# as14120_x31_fpga_ddr.net
KiCad netlist of a schematic drawn in Altium Designer
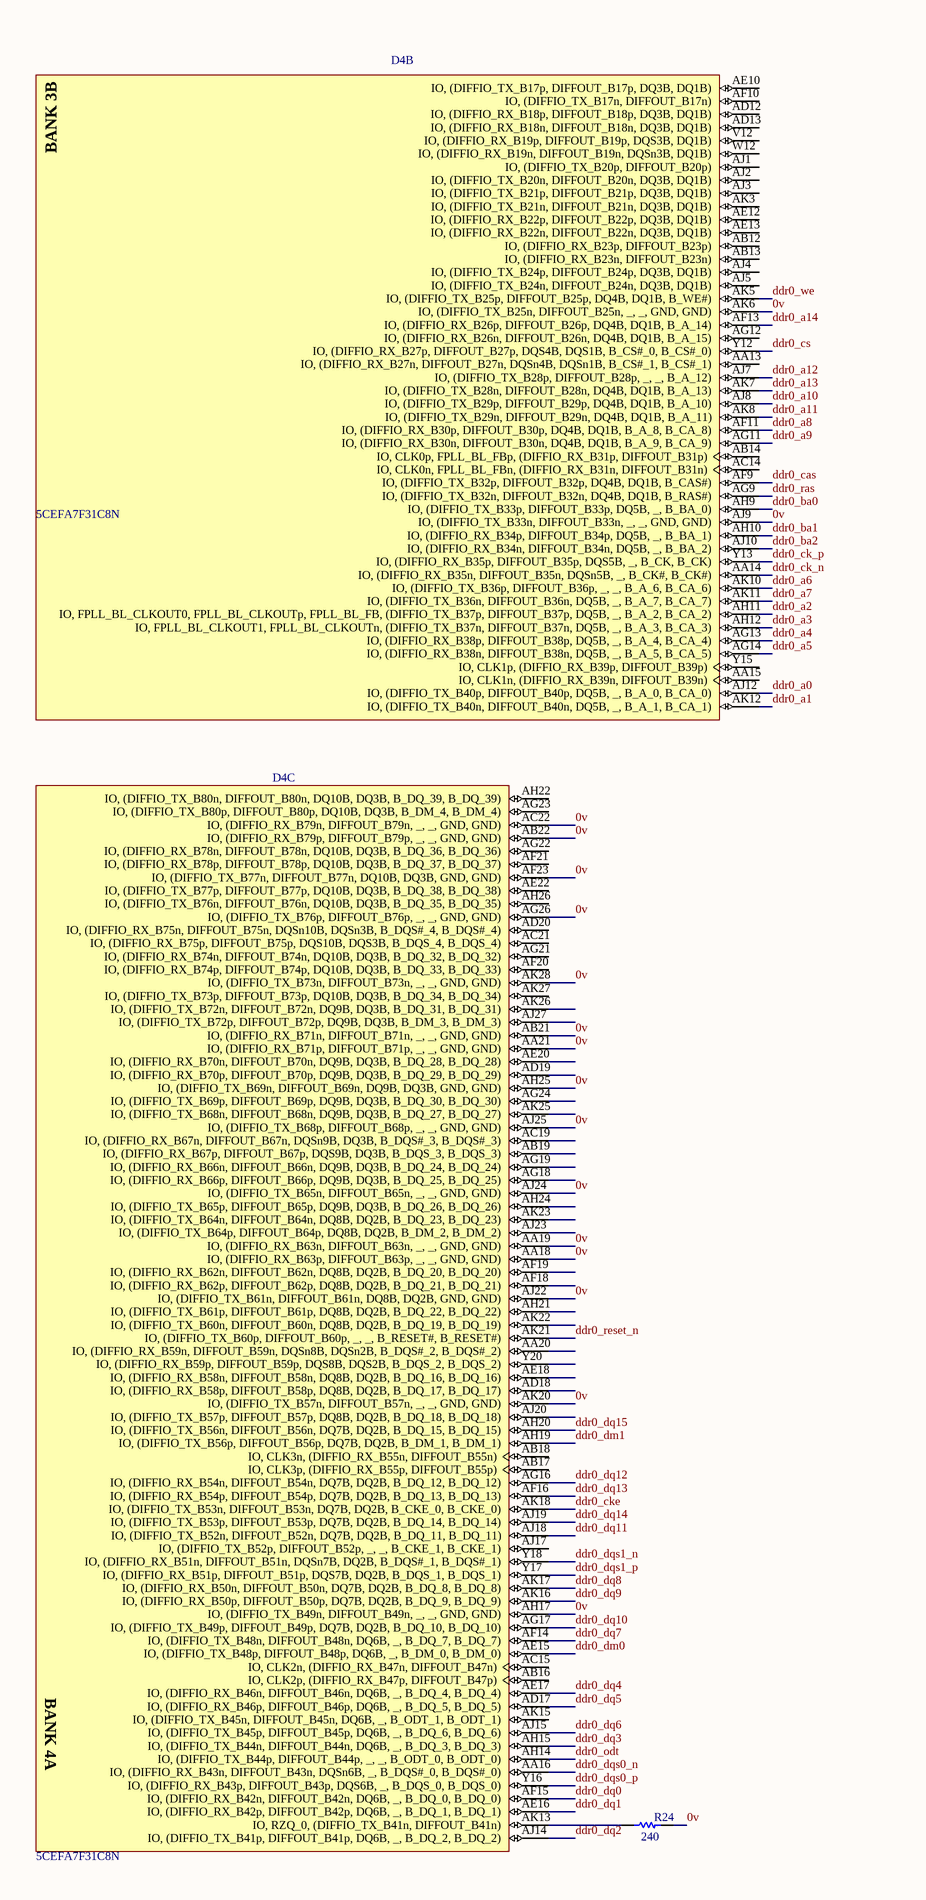
[diagram p0: as14120_x31_fpga_ddr.SchDoc, left]
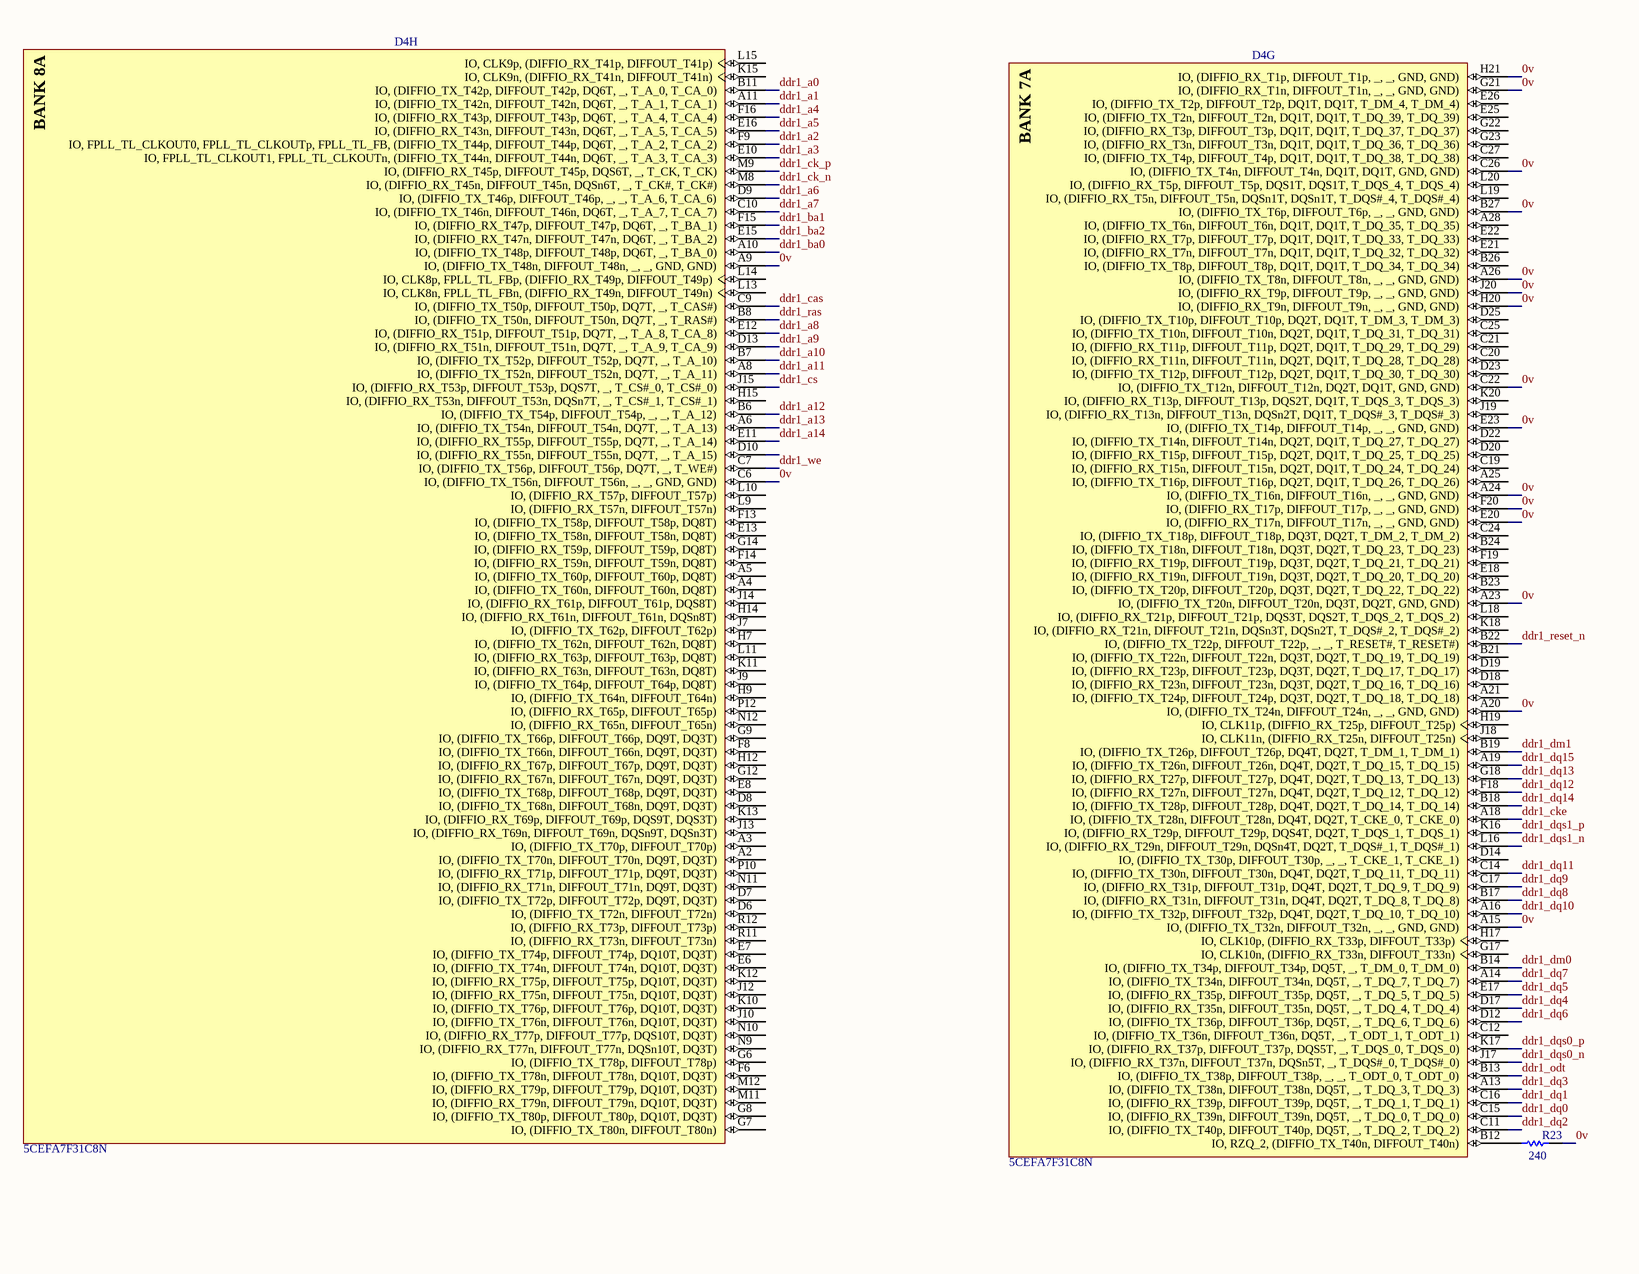
[diagram p1: as14120_x31_fpga_ddr.SchDoc, right]

(export (version "E")
  (design (tool "Eeschema 10.0.6"))
  (components
    (comp (ref "D4")
      (value "5CEFA7F31C8N")
      (footprint "ALTR-896-FBGA-2000A")
      (fields (field (name "MANUFACTURER") "Altera"))
      (libsource (lib "Altera Cyclone V E") (part "5CEFA7F31C8N"))
    )
    (comp (ref "R23")
      (value "240")
      (footprint "RESC0805(2012)_L")
      (description "1K 0.125W 1% 0805 (2012 Metric)  SMD")
      (fields (field (name "TOLERANCE") "1 %") (field (name "POWER") "0.125 W"))
      (libsource (lib "as14120") (part "RES_0805"))
    )
    (comp (ref "R24")
      (value "240")
      (footprint "RESC0805(2012)_L")
      (description "1K 0.125W 1% 0805 (2012 Metric)  SMD")
      (fields (field (name "TOLERANCE") "1 %") (field (name "POWER") "0.125 W"))
      (libsource (lib "as14120") (part "RES_0805"))
    )
  )
  (nets
    (net (code "1") (name "/0v") (class "Default")
      (node (ref "D4") (pin "A15") (pinfunction "IO,_(DIFFIO_TX_T32n,_DIFFOUT_T32n,__,__,_GND,_GND)_A15") (pintype "bidirectional"))
      (node (ref "D4") (pin "A20") (pinfunction "IO,_(DIFFIO_TX_T24n,_DIFFOUT_T24n,__,__,_GND,_GND)_A20") (pintype "bidirectional"))
      (node (ref "D4") (pin "A23") (pinfunction "IO,_(DIFFIO_TX_T20n,_DIFFOUT_T20n,_DQ3T,_DQ2T,_GND,_GND)_A23") (pintype "bidirectional"))
      (node (ref "D4") (pin "A24") (pinfunction "IO,_(DIFFIO_TX_T16n,_DIFFOUT_T16n,__,__,_GND,_GND)_A24") (pintype "bidirectional"))
      (node (ref "D4") (pin "A26") (pinfunction "IO,_(DIFFIO_TX_T8n,_DIFFOUT_T8n,__,__,_GND,_GND)_A26") (pintype "bidirectional"))
      (node (ref "D4") (pin "A9") (pinfunction "IO,_(DIFFIO_TX_T48n,_DIFFOUT_T48n,__,__,_GND,_GND)_A9") (pintype "bidirectional"))
      (node (ref "D4") (pin "AA18") (pinfunction "IO,_(DIFFIO_RX_B63p,_DIFFOUT_B63p,__,__,_GND,_GND)_AA18") (pintype "bidirectional"))
      (node (ref "D4") (pin "AA19") (pinfunction "IO,_(DIFFIO_RX_B63n,_DIFFOUT_B63n,__,__,_GND,_GND)_AA19") (pintype "bidirectional"))
      (node (ref "D4") (pin "AA21") (pinfunction "IO,_(DIFFIO_RX_B71p,_DIFFOUT_B71p,__,__,_GND,_GND)_AA21") (pintype "bidirectional"))
      (node (ref "D4") (pin "AB21") (pinfunction "IO,_(DIFFIO_RX_B71n,_DIFFOUT_B71n,__,__,_GND,_GND)_AB21") (pintype "bidirectional"))
      (node (ref "D4") (pin "AB22") (pinfunction "IO,_(DIFFIO_RX_B79p,_DIFFOUT_B79p,__,__,_GND,_GND)_AB22") (pintype "bidirectional"))
      (node (ref "D4") (pin "AC22") (pinfunction "IO,_(DIFFIO_RX_B79n,_DIFFOUT_B79n,__,__,_GND,_GND)_AC22") (pintype "bidirectional"))
      (node (ref "D4") (pin "AF23") (pinfunction "IO,_(DIFFIO_TX_B77n,_DIFFOUT_B77n,_DQ10B,_DQ3B,_GND,_GND)_AF23") (pintype "bidirectional"))
      (node (ref "D4") (pin "AG26") (pinfunction "IO,_(DIFFIO_TX_B76p,_DIFFOUT_B76p,__,__,_GND,_GND)_AG26") (pintype "bidirectional"))
      (node (ref "D4") (pin "AH17") (pinfunction "IO,_(DIFFIO_TX_B49n,_DIFFOUT_B49n,__,__,_GND,_GND)_AH17") (pintype "bidirectional"))
      (node (ref "D4") (pin "AH25") (pinfunction "IO,_(DIFFIO_TX_B69n,_DIFFOUT_B69n,_DQ9B,_DQ3B,_GND,_GND)_AH25") (pintype "bidirectional"))
      (node (ref "D4") (pin "AJ22") (pinfunction "IO,_(DIFFIO_TX_B61n,_DIFFOUT_B61n,_DQ8B,_DQ2B,_GND,_GND)_AJ22") (pintype "bidirectional"))
      (node (ref "D4") (pin "AJ24") (pinfunction "IO,_(DIFFIO_TX_B65n,_DIFFOUT_B65n,__,__,_GND,_GND)_AJ24") (pintype "bidirectional"))
      (node (ref "D4") (pin "AJ25") (pinfunction "IO,_(DIFFIO_TX_B68p,_DIFFOUT_B68p,__,__,_GND,_GND)_AJ25") (pintype "bidirectional"))
      (node (ref "D4") (pin "AJ9") (pinfunction "IO,_(DIFFIO_TX_B33n,_DIFFOUT_B33n,__,__,_GND,_GND)_AJ9") (pintype "bidirectional"))
      (node (ref "D4") (pin "AK20") (pinfunction "IO,_(DIFFIO_TX_B57n,_DIFFOUT_B57n,__,__,_GND,_GND)_AK20") (pintype "bidirectional"))
      (node (ref "D4") (pin "AK28") (pinfunction "IO,_(DIFFIO_TX_B73n,_DIFFOUT_B73n,__,__,_GND,_GND)_AK28") (pintype "bidirectional"))
      (node (ref "D4") (pin "AK6") (pinfunction "IO,_(DIFFIO_TX_B25n,_DIFFOUT_B25n,__,__,_GND,_GND)_AK6") (pintype "bidirectional"))
      (node (ref "D4") (pin "B27") (pinfunction "IO,_(DIFFIO_TX_T6p,_DIFFOUT_T6p,__,__,_GND,_GND)_B27") (pintype "bidirectional"))
      (node (ref "D4") (pin "C22") (pinfunction "IO,_(DIFFIO_TX_T12n,_DIFFOUT_T12n,_DQ2T,_DQ1T,_GND,_GND)_C22") (pintype "bidirectional"))
      (node (ref "D4") (pin "C26") (pinfunction "IO,_(DIFFIO_TX_T4n,_DIFFOUT_T4n,_DQ1T,_DQ1T,_GND,_GND)_C26") (pintype "bidirectional"))
      (node (ref "D4") (pin "C6") (pinfunction "IO,_(DIFFIO_TX_T56n,_DIFFOUT_T56n,__,__,_GND,_GND)_C6") (pintype "bidirectional"))
      (node (ref "D4") (pin "E20") (pinfunction "IO,_(DIFFIO_RX_T17n,_DIFFOUT_T17n,__,__,_GND,_GND)_E20") (pintype "bidirectional"))
      (node (ref "D4") (pin "E23") (pinfunction "IO,_(DIFFIO_TX_T14p,_DIFFOUT_T14p,__,__,_GND,_GND)_E23") (pintype "bidirectional"))
      (node (ref "D4") (pin "F20") (pinfunction "IO,_(DIFFIO_RX_T17p,_DIFFOUT_T17p,__,__,_GND,_GND)_F20") (pintype "bidirectional"))
      (node (ref "D4") (pin "G21") (pinfunction "IO,_(DIFFIO_RX_T1n,_DIFFOUT_T1n,__,__,_GND,_GND)_G21") (pintype "bidirectional"))
      (node (ref "D4") (pin "H20") (pinfunction "IO,_(DIFFIO_RX_T9n,_DIFFOUT_T9n,__,__,_GND,_GND)_H20") (pintype "bidirectional"))
      (node (ref "D4") (pin "H21") (pinfunction "IO,_(DIFFIO_RX_T1p,_DIFFOUT_T1p,__,__,_GND,_GND)_H21") (pintype "bidirectional"))
      (node (ref "D4") (pin "J20") (pinfunction "IO,_(DIFFIO_RX_T9p,_DIFFOUT_T9p,__,__,_GND,_GND)_J20") (pintype "bidirectional"))
      (node (ref "R23") (pin "2") (pinfunction "2_2") (pintype "passive"))
      (node (ref "R24") (pin "2") (pinfunction "2_2") (pintype "passive"))
    )
    (net (code "2") (name "/ddr0_a0") (class "Default")
      (node (ref "D4") (pin "AJ12") (pinfunction "IO,_(DIFFIO_TX_B40p,_DIFFOUT_B40p,_DQ5B,__,_B_A_0,_B_CA_0)_AJ12") (pintype "bidirectional"))
    )
    (net (code "3") (name "/ddr0_a1") (class "Default")
      (node (ref "D4") (pin "AK12") (pinfunction "IO,_(DIFFIO_TX_B40n,_DIFFOUT_B40n,_DQ5B,__,_B_A_1,_B_CA_1)_AK12") (pintype "bidirectional"))
    )
    (net (code "4") (name "/ddr0_a2") (class "Default")
      (node (ref "D4") (pin "AH11") (pinfunction "IO,_FPLL_BL_CLKOUT0,_FPLL_BL_CLKOUTp,_FPLL_BL_FB,_(DIFFIO_TX_B37p,_DIFFOUT_B37p,_DQ5B,__,_B_A_2,_B_CA_2)_AH11") (pintype "bidirectional"))
    )
    (net (code "5") (name "/ddr0_a3") (class "Default")
      (node (ref "D4") (pin "AH12") (pinfunction "IO,_FPLL_BL_CLKOUT1,_FPLL_BL_CLKOUTn,_(DIFFIO_TX_B37n,_DIFFOUT_B37n,_DQ5B,__,_B_A_3,_B_CA_3)_AH12") (pintype "bidirectional"))
    )
    (net (code "6") (name "/ddr0_a4") (class "Default")
      (node (ref "D4") (pin "AG13") (pinfunction "IO,_(DIFFIO_RX_B38p,_DIFFOUT_B38p,_DQ5B,__,_B_A_4,_B_CA_4)_AG13") (pintype "bidirectional"))
    )
    (net (code "7") (name "/ddr0_a5") (class "Default")
      (node (ref "D4") (pin "AG14") (pinfunction "IO,_(DIFFIO_RX_B38n,_DIFFOUT_B38n,_DQ5B,__,_B_A_5,_B_CA_5)_AG14") (pintype "bidirectional"))
    )
    (net (code "8") (name "/ddr0_a6") (class "Default")
      (node (ref "D4") (pin "AK10") (pinfunction "IO,_(DIFFIO_TX_B36p,_DIFFOUT_B36p,__,__,_B_A_6,_B_CA_6)_AK10") (pintype "bidirectional"))
    )
    (net (code "9") (name "/ddr0_a7") (class "Default")
      (node (ref "D4") (pin "AK11") (pinfunction "IO,_(DIFFIO_TX_B36n,_DIFFOUT_B36n,_DQ5B,__,_B_A_7,_B_CA_7)_AK11") (pintype "bidirectional"))
    )
    (net (code "10") (name "/ddr0_a8") (class "Default")
      (node (ref "D4") (pin "AF11") (pinfunction "IO,_(DIFFIO_RX_B30p,_DIFFOUT_B30p,_DQ4B,_DQ1B,_B_A_8,_B_CA_8)_AF11") (pintype "bidirectional"))
    )
    (net (code "11") (name "/ddr0_a9") (class "Default")
      (node (ref "D4") (pin "AG11") (pinfunction "IO,_(DIFFIO_RX_B30n,_DIFFOUT_B30n,_DQ4B,_DQ1B,_B_A_9,_B_CA_9)_AG11") (pintype "bidirectional"))
    )
    (net (code "12") (name "/ddr0_a10") (class "Default")
      (node (ref "D4") (pin "AJ8") (pinfunction "IO,_(DIFFIO_TX_B29p,_DIFFOUT_B29p,_DQ4B,_DQ1B,_B_A_10)_AJ8") (pintype "bidirectional"))
    )
    (net (code "13") (name "/ddr0_a11") (class "Default")
      (node (ref "D4") (pin "AK8") (pinfunction "IO,_(DIFFIO_TX_B29n,_DIFFOUT_B29n,_DQ4B,_DQ1B,_B_A_11)_AK8") (pintype "bidirectional"))
    )
    (net (code "14") (name "/ddr0_a12") (class "Default")
      (node (ref "D4") (pin "AJ7") (pinfunction "IO,_(DIFFIO_TX_B28p,_DIFFOUT_B28p,__,__,_B_A_12)_AJ7") (pintype "bidirectional"))
    )
    (net (code "15") (name "/ddr0_a13") (class "Default")
      (node (ref "D4") (pin "AK7") (pinfunction "IO,_(DIFFIO_TX_B28n,_DIFFOUT_B28n,_DQ4B,_DQ1B,_B_A_13)_AK7") (pintype "bidirectional"))
    )
    (net (code "16") (name "/ddr0_a14") (class "Default")
      (node (ref "D4") (pin "AF13") (pinfunction "IO,_(DIFFIO_RX_B26p,_DIFFOUT_B26p,_DQ4B,_DQ1B,_B_A_14)_AF13") (pintype "bidirectional"))
    )
    (net (code "17") (name "/ddr0_ba0") (class "Default")
      (node (ref "D4") (pin "AH9") (pinfunction "IO,_(DIFFIO_TX_B33p,_DIFFOUT_B33p,_DQ5B,__,_B_BA_0)_AH9") (pintype "bidirectional"))
    )
    (net (code "18") (name "/ddr0_ba1") (class "Default")
      (node (ref "D4") (pin "AH10") (pinfunction "IO,_(DIFFIO_RX_B34p,_DIFFOUT_B34p,_DQ5B,__,_B_BA_1)_AH10") (pintype "bidirectional"))
    )
    (net (code "19") (name "/ddr0_ba2") (class "Default")
      (node (ref "D4") (pin "AJ10") (pinfunction "IO,_(DIFFIO_RX_B34n,_DIFFOUT_B34n,_DQ5B,__,_B_BA_2)_AJ10") (pintype "bidirectional"))
    )
    (net (code "20") (name "/ddr0_cas") (class "Default")
      (node (ref "D4") (pin "AF9") (pinfunction "IO,_(DIFFIO_TX_B32p,_DIFFOUT_B32p,_DQ4B,_DQ1B,_B_CAS#)_AF9") (pintype "bidirectional"))
    )
    (net (code "21") (name "/ddr0_ck_n") (class "Default")
      (node (ref "D4") (pin "AA14") (pinfunction "IO,_(DIFFIO_RX_B35n,_DIFFOUT_B35n,_DQSn5B,__,_B_CK#,_B_CK#)_AA14") (pintype "bidirectional"))
    )
    (net (code "22") (name "/ddr0_ck_p") (class "Default")
      (node (ref "D4") (pin "Y13") (pinfunction "IO,_(DIFFIO_RX_B35p,_DIFFOUT_B35p,_DQS5B,__,_B_CK,_B_CK)_Y13") (pintype "bidirectional"))
    )
    (net (code "23") (name "/ddr0_cke") (class "Default")
      (node (ref "D4") (pin "AK18") (pinfunction "IO,_(DIFFIO_TX_B53n,_DIFFOUT_B53n,_DQ7B,_DQ2B,_B_CKE_0,_B_CKE_0)_AK18") (pintype "bidirectional"))
    )
    (net (code "24") (name "/ddr0_cs") (class "Default")
      (node (ref "D4") (pin "Y12") (pinfunction "IO,_(DIFFIO_RX_B27p,_DIFFOUT_B27p,_DQS4B,_DQS1B,_B_CS#_0,_B_CS#_0)_Y12") (pintype "bidirectional"))
    )
    (net (code "25") (name "/ddr0_dm0") (class "Default")
      (node (ref "D4") (pin "AE15") (pinfunction "IO,_(DIFFIO_TX_B48p,_DIFFOUT_B48p,_DQ6B,__,_B_DM_0,_B_DM_0)_AE15") (pintype "bidirectional"))
    )
    (net (code "26") (name "/ddr0_dm1") (class "Default")
      (node (ref "D4") (pin "AH19") (pinfunction "IO,_(DIFFIO_TX_B56p,_DIFFOUT_B56p,_DQ7B,_DQ2B,_B_DM_1,_B_DM_1)_AH19") (pintype "bidirectional"))
    )
    (net (code "27") (name "/ddr0_dq0") (class "Default")
      (node (ref "D4") (pin "AF15") (pinfunction "IO,_(DIFFIO_RX_B42n,_DIFFOUT_B42n,_DQ6B,__,_B_DQ_0,_B_DQ_0)_AF15") (pintype "bidirectional"))
    )
    (net (code "28") (name "/ddr0_dq1") (class "Default")
      (node (ref "D4") (pin "AE16") (pinfunction "IO,_(DIFFIO_RX_B42p,_DIFFOUT_B42p,_DQ6B,__,_B_DQ_1,_B_DQ_1)_AE16") (pintype "bidirectional"))
    )
    (net (code "29") (name "/ddr0_dq2") (class "Default")
      (node (ref "D4") (pin "AJ14") (pinfunction "IO,_(DIFFIO_TX_B41p,_DIFFOUT_B41p,_DQ6B,__,_B_DQ_2,_B_DQ_2)_AJ14") (pintype "bidirectional"))
    )
    (net (code "30") (name "/ddr0_dq3") (class "Default")
      (node (ref "D4") (pin "AH15") (pinfunction "IO,_(DIFFIO_TX_B44n,_DIFFOUT_B44n,_DQ6B,__,_B_DQ_3,_B_DQ_3)_AH15") (pintype "bidirectional"))
    )
    (net (code "31") (name "/ddr0_dq4") (class "Default")
      (node (ref "D4") (pin "AE17") (pinfunction "IO,_(DIFFIO_RX_B46n,_DIFFOUT_B46n,_DQ6B,__,_B_DQ_4,_B_DQ_4)_AE17") (pintype "bidirectional"))
    )
    (net (code "32") (name "/ddr0_dq5") (class "Default")
      (node (ref "D4") (pin "AD17") (pinfunction "IO,_(DIFFIO_RX_B46p,_DIFFOUT_B46p,_DQ6B,__,_B_DQ_5,_B_DQ_5)_AD17") (pintype "bidirectional"))
    )
    (net (code "33") (name "/ddr0_dq6") (class "Default")
      (node (ref "D4") (pin "AJ15") (pinfunction "IO,_(DIFFIO_TX_B45p,_DIFFOUT_B45p,_DQ6B,__,_B_DQ_6,_B_DQ_6)_AJ15") (pintype "bidirectional"))
    )
    (net (code "34") (name "/ddr0_dq7") (class "Default")
      (node (ref "D4") (pin "AF14") (pinfunction "IO,_(DIFFIO_TX_B48n,_DIFFOUT_B48n,_DQ6B,__,_B_DQ_7,_B_DQ_7)_AF14") (pintype "bidirectional"))
    )
    (net (code "35") (name "/ddr0_dq8") (class "Default")
      (node (ref "D4") (pin "AK17") (pinfunction "IO,_(DIFFIO_RX_B50n,_DIFFOUT_B50n,_DQ7B,_DQ2B,_B_DQ_8,_B_DQ_8)_AK17") (pintype "bidirectional"))
    )
    (net (code "36") (name "/ddr0_dq9") (class "Default")
      (node (ref "D4") (pin "AK16") (pinfunction "IO,_(DIFFIO_RX_B50p,_DIFFOUT_B50p,_DQ7B,_DQ2B,_B_DQ_9,_B_DQ_9)_AK16") (pintype "bidirectional"))
    )
    (net (code "37") (name "/ddr0_dq10") (class "Default")
      (node (ref "D4") (pin "AG17") (pinfunction "IO,_(DIFFIO_TX_B49p,_DIFFOUT_B49p,_DQ7B,_DQ2B,_B_DQ_10,_B_DQ_10)_AG17") (pintype "bidirectional"))
    )
    (net (code "38") (name "/ddr0_dq11") (class "Default")
      (node (ref "D4") (pin "AJ18") (pinfunction "IO,_(DIFFIO_TX_B52n,_DIFFOUT_B52n,_DQ7B,_DQ2B,_B_DQ_11,_B_DQ_11)_AJ18") (pintype "bidirectional"))
    )
    (net (code "39") (name "/ddr0_dq12") (class "Default")
      (node (ref "D4") (pin "AG16") (pinfunction "IO,_(DIFFIO_RX_B54n,_DIFFOUT_B54n,_DQ7B,_DQ2B,_B_DQ_12,_B_DQ_12)_AG16") (pintype "bidirectional"))
    )
    (net (code "40") (name "/ddr0_dq13") (class "Default")
      (node (ref "D4") (pin "AF16") (pinfunction "IO,_(DIFFIO_RX_B54p,_DIFFOUT_B54p,_DQ7B,_DQ2B,_B_DQ_13,_B_DQ_13)_AF16") (pintype "bidirectional"))
    )
    (net (code "41") (name "/ddr0_dq14") (class "Default")
      (node (ref "D4") (pin "AJ19") (pinfunction "IO,_(DIFFIO_TX_B53p,_DIFFOUT_B53p,_DQ7B,_DQ2B,_B_DQ_14,_B_DQ_14)_AJ19") (pintype "bidirectional"))
    )
    (net (code "42") (name "/ddr0_dq15") (class "Default")
      (node (ref "D4") (pin "AH20") (pinfunction "IO,_(DIFFIO_TX_B56n,_DIFFOUT_B56n,_DQ7B,_DQ2B,_B_DQ_15,_B_DQ_15)_AH20") (pintype "bidirectional"))
    )
    (net (code "43") (name "/ddr0_dqs0_n") (class "Default")
      (node (ref "D4") (pin "AA16") (pinfunction "IO,_(DIFFIO_RX_B43n,_DIFFOUT_B43n,_DQSn6B,__,_B_DQS#_0,_B_DQS#_0)_AA16") (pintype "bidirectional"))
    )
    (net (code "44") (name "/ddr0_dqs0_p") (class "Default")
      (node (ref "D4") (pin "Y16") (pinfunction "IO,_(DIFFIO_RX_B43p,_DIFFOUT_B43p,_DQS6B,__,_B_DQS_0,_B_DQS_0)_Y16") (pintype "bidirectional"))
    )
    (net (code "45") (name "/ddr0_dqs1_n") (class "Default")
      (node (ref "D4") (pin "Y18") (pinfunction "IO,_(DIFFIO_RX_B51n,_DIFFOUT_B51n,_DQSn7B,_DQ2B,_B_DQS#_1,_B_DQS#_1)_Y18") (pintype "bidirectional"))
    )
    (net (code "46") (name "/ddr0_dqs1_p") (class "Default")
      (node (ref "D4") (pin "Y17") (pinfunction "IO,_(DIFFIO_RX_B51p,_DIFFOUT_B51p,_DQS7B,_DQ2B,_B_DQS_1,_B_DQS_1)_Y17") (pintype "bidirectional"))
    )
    (net (code "47") (name "/ddr0_odt") (class "Default")
      (node (ref "D4") (pin "AH14") (pinfunction "IO,_(DIFFIO_TX_B44p,_DIFFOUT_B44p,__,__,_B_ODT_0,_B_ODT_0)_AH14") (pintype "bidirectional"))
    )
    (net (code "48") (name "/ddr0_ras") (class "Default")
      (node (ref "D4") (pin "AG9") (pinfunction "IO,_(DIFFIO_TX_B32n,_DIFFOUT_B32n,_DQ4B,_DQ1B,_B_RAS#)_AG9") (pintype "bidirectional"))
    )
    (net (code "49") (name "/ddr0_reset_n") (class "Default")
      (node (ref "D4") (pin "AK21") (pinfunction "IO,_(DIFFIO_TX_B60p,_DIFFOUT_B60p,__,__,_B_RESET#,_B_RESET#)_AK21") (pintype "bidirectional"))
    )
    (net (code "50") (name "/ddr0_we") (class "Default")
      (node (ref "D4") (pin "AK5") (pinfunction "IO,_(DIFFIO_TX_B25p,_DIFFOUT_B25p,_DQ4B,_DQ1B,_B_WE#)_AK5") (pintype "bidirectional"))
    )
    (net (code "51") (name "/ddr1_a0") (class "Default")
      (node (ref "D4") (pin "B11") (pinfunction "IO,_(DIFFIO_TX_T42p,_DIFFOUT_T42p,_DQ6T,__,_T_A_0,_T_CA_0)_B11") (pintype "bidirectional"))
    )
    (net (code "52") (name "/ddr1_a1") (class "Default")
      (node (ref "D4") (pin "A11") (pinfunction "IO,_(DIFFIO_TX_T42n,_DIFFOUT_T42n,_DQ6T,__,_T_A_1,_T_CA_1)_A11") (pintype "bidirectional"))
    )
    (net (code "53") (name "/ddr1_a2") (class "Default")
      (node (ref "D4") (pin "F9") (pinfunction "IO,_FPLL_TL_CLKOUT0,_FPLL_TL_CLKOUTp,_FPLL_TL_FB,_(DIFFIO_TX_T44p,_DIFFOUT_T44p,_DQ6T,__,_T_A_2,_T_CA_2)_F9") (pintype "bidirectional"))
    )
    (net (code "54") (name "/ddr1_a3") (class "Default")
      (node (ref "D4") (pin "E10") (pinfunction "IO,_FPLL_TL_CLKOUT1,_FPLL_TL_CLKOUTn,_(DIFFIO_TX_T44n,_DIFFOUT_T44n,_DQ6T,__,_T_A_3,_T_CA_3)_E10") (pintype "bidirectional"))
    )
    (net (code "55") (name "/ddr1_a4") (class "Default")
      (node (ref "D4") (pin "F16") (pinfunction "IO,_(DIFFIO_RX_T43p,_DIFFOUT_T43p,_DQ6T,__,_T_A_4,_T_CA_4)_F16") (pintype "bidirectional"))
    )
    (net (code "56") (name "/ddr1_a5") (class "Default")
      (node (ref "D4") (pin "E16") (pinfunction "IO,_(DIFFIO_RX_T43n,_DIFFOUT_T43n,_DQ6T,__,_T_A_5,_T_CA_5)_E16") (pintype "bidirectional"))
    )
    (net (code "57") (name "/ddr1_a6") (class "Default")
      (node (ref "D4") (pin "D9") (pinfunction "IO,_(DIFFIO_TX_T46p,_DIFFOUT_T46p,__,__,_T_A_6,_T_CA_6)_D9") (pintype "bidirectional"))
    )
    (net (code "58") (name "/ddr1_a7") (class "Default")
      (node (ref "D4") (pin "C10") (pinfunction "IO,_(DIFFIO_TX_T46n,_DIFFOUT_T46n,_DQ6T,__,_T_A_7,_T_CA_7)_C10") (pintype "bidirectional"))
    )
    (net (code "59") (name "/ddr1_a8") (class "Default")
      (node (ref "D4") (pin "E12") (pinfunction "IO,_(DIFFIO_RX_T51p,_DIFFOUT_T51p,_DQ7T,__,_T_A_8,_T_CA_8)_E12") (pintype "bidirectional"))
    )
    (net (code "60") (name "/ddr1_a9") (class "Default")
      (node (ref "D4") (pin "D13") (pinfunction "IO,_(DIFFIO_RX_T51n,_DIFFOUT_T51n,_DQ7T,__,_T_A_9,_T_CA_9)_D13") (pintype "bidirectional"))
    )
    (net (code "61") (name "/ddr1_a10") (class "Default")
      (node (ref "D4") (pin "B7") (pinfunction "IO,_(DIFFIO_TX_T52p,_DIFFOUT_T52p,_DQ7T,__,_T_A_10)_B7") (pintype "bidirectional"))
    )
    (net (code "62") (name "/ddr1_a11") (class "Default")
      (node (ref "D4") (pin "A8") (pinfunction "IO,_(DIFFIO_TX_T52n,_DIFFOUT_T52n,_DQ7T,__,_T_A_11)_A8") (pintype "bidirectional"))
    )
    (net (code "63") (name "/ddr1_a12") (class "Default")
      (node (ref "D4") (pin "B6") (pinfunction "IO,_(DIFFIO_TX_T54p,_DIFFOUT_T54p,__,__,_T_A_12)_B6") (pintype "bidirectional"))
    )
    (net (code "64") (name "/ddr1_a13") (class "Default")
      (node (ref "D4") (pin "A6") (pinfunction "IO,_(DIFFIO_TX_T54n,_DIFFOUT_T54n,_DQ7T,__,_T_A_13)_A6") (pintype "bidirectional"))
    )
    (net (code "65") (name "/ddr1_a14") (class "Default")
      (node (ref "D4") (pin "E11") (pinfunction "IO,_(DIFFIO_RX_T55p,_DIFFOUT_T55p,_DQ7T,__,_T_A_14)_E11") (pintype "bidirectional"))
    )
    (net (code "66") (name "/ddr1_ba0") (class "Default")
      (node (ref "D4") (pin "A10") (pinfunction "IO,_(DIFFIO_TX_T48p,_DIFFOUT_T48p,_DQ6T,__,_T_BA_0)_A10") (pintype "bidirectional"))
    )
    (net (code "67") (name "/ddr1_ba1") (class "Default")
      (node (ref "D4") (pin "F15") (pinfunction "IO,_(DIFFIO_RX_T47p,_DIFFOUT_T47p,_DQ6T,__,_T_BA_1)_F15") (pintype "bidirectional"))
    )
    (net (code "68") (name "/ddr1_ba2") (class "Default")
      (node (ref "D4") (pin "E15") (pinfunction "IO,_(DIFFIO_RX_T47n,_DIFFOUT_T47n,_DQ6T,__,_T_BA_2)_E15") (pintype "bidirectional"))
    )
    (net (code "69") (name "/ddr1_cas") (class "Default")
      (node (ref "D4") (pin "C9") (pinfunction "IO,_(DIFFIO_TX_T50p,_DIFFOUT_T50p,_DQ7T,__,_T_CAS#)_C9") (pintype "bidirectional"))
    )
    (net (code "70") (name "/ddr1_ck_n") (class "Default")
      (node (ref "D4") (pin "M8") (pinfunction "IO,_(DIFFIO_RX_T45n,_DIFFOUT_T45n,_DQSn6T,__,_T_CK#,_T_CK#)_M8") (pintype "bidirectional"))
    )
    (net (code "71") (name "/ddr1_ck_p") (class "Default")
      (node (ref "D4") (pin "M9") (pinfunction "IO,_(DIFFIO_RX_T45p,_DIFFOUT_T45p,_DQS6T,__,_T_CK,_T_CK)_M9") (pintype "bidirectional"))
    )
    (net (code "72") (name "/ddr1_cke") (class "Default")
      (node (ref "D4") (pin "A18") (pinfunction "IO,_(DIFFIO_TX_T28n,_DIFFOUT_T28n,_DQ4T,_DQ2T,_T_CKE_0,_T_CKE_0)_A18") (pintype "bidirectional"))
    )
    (net (code "73") (name "/ddr1_cs") (class "Default")
      (node (ref "D4") (pin "J15") (pinfunction "IO,_(DIFFIO_RX_T53p,_DIFFOUT_T53p,_DQS7T,__,_T_CS#_0,_T_CS#_0)_J15") (pintype "bidirectional"))
    )
    (net (code "74") (name "/ddr1_dm0") (class "Default")
      (node (ref "D4") (pin "B14") (pinfunction "IO,_(DIFFIO_TX_T34p,_DIFFOUT_T34p,_DQ5T,__,_T_DM_0,_T_DM_0)_B14") (pintype "bidirectional"))
    )
    (net (code "75") (name "/ddr1_dm1") (class "Default")
      (node (ref "D4") (pin "B19") (pinfunction "IO,_(DIFFIO_TX_T26p,_DIFFOUT_T26p,_DQ4T,_DQ2T,_T_DM_1,_T_DM_1)_B19") (pintype "bidirectional"))
    )
    (net (code "76") (name "/ddr1_dq0") (class "Default")
      (node (ref "D4") (pin "C15") (pinfunction "IO,_(DIFFIO_RX_T39n,_DIFFOUT_T39n,_DQ5T,__,_T_DQ_0,_T_DQ_0)_C15") (pintype "bidirectional"))
    )
    (net (code "77") (name "/ddr1_dq1") (class "Default")
      (node (ref "D4") (pin "C16") (pinfunction "IO,_(DIFFIO_RX_T39p,_DIFFOUT_T39p,_DQ5T,__,_T_DQ_1,_T_DQ_1)_C16") (pintype "bidirectional"))
    )
    (net (code "78") (name "/ddr1_dq2") (class "Default")
      (node (ref "D4") (pin "C11") (pinfunction "IO,_(DIFFIO_TX_T40p,_DIFFOUT_T40p,_DQ5T,__,_T_DQ_2,_T_DQ_2)_C11") (pintype "bidirectional"))
    )
    (net (code "79") (name "/ddr1_dq3") (class "Default")
      (node (ref "D4") (pin "A13") (pinfunction "IO,_(DIFFIO_TX_T38n,_DIFFOUT_T38n,_DQ5T,__,_T_DQ_3,_T_DQ_3)_A13") (pintype "bidirectional"))
    )
    (net (code "80") (name "/ddr1_dq4") (class "Default")
      (node (ref "D4") (pin "D17") (pinfunction "IO,_(DIFFIO_RX_T35n,_DIFFOUT_T35n,_DQ5T,__,_T_DQ_4,_T_DQ_4)_D17") (pintype "bidirectional"))
    )
    (net (code "81") (name "/ddr1_dq5") (class "Default")
      (node (ref "D4") (pin "E17") (pinfunction "IO,_(DIFFIO_RX_T35p,_DIFFOUT_T35p,_DQ5T,__,_T_DQ_5,_T_DQ_5)_E17") (pintype "bidirectional"))
    )
    (net (code "82") (name "/ddr1_dq6") (class "Default")
      (node (ref "D4") (pin "D12") (pinfunction "IO,_(DIFFIO_TX_T36p,_DIFFOUT_T36p,_DQ5T,__,_T_DQ_6,_T_DQ_6)_D12") (pintype "bidirectional"))
    )
    (net (code "83") (name "/ddr1_dq7") (class "Default")
      (node (ref "D4") (pin "A14") (pinfunction "IO,_(DIFFIO_TX_T34n,_DIFFOUT_T34n,_DQ5T,__,_T_DQ_7,_T_DQ_7)_A14") (pintype "bidirectional"))
    )
    (net (code "84") (name "/ddr1_dq8") (class "Default")
      (node (ref "D4") (pin "B17") (pinfunction "IO,_(DIFFIO_RX_T31n,_DIFFOUT_T31n,_DQ4T,_DQ2T,_T_DQ_8,_T_DQ_8)_B17") (pintype "bidirectional"))
    )
    (net (code "85") (name "/ddr1_dq9") (class "Default")
      (node (ref "D4") (pin "C17") (pinfunction "IO,_(DIFFIO_RX_T31p,_DIFFOUT_T31p,_DQ4T,_DQ2T,_T_DQ_9,_T_DQ_9)_C17") (pintype "bidirectional"))
    )
    (net (code "86") (name "/ddr1_dq10") (class "Default")
      (node (ref "D4") (pin "A16") (pinfunction "IO,_(DIFFIO_TX_T32p,_DIFFOUT_T32p,_DQ4T,_DQ2T,_T_DQ_10,_T_DQ_10)_A16") (pintype "bidirectional"))
    )
    (net (code "87") (name "/ddr1_dq11") (class "Default")
      (node (ref "D4") (pin "C14") (pinfunction "IO,_(DIFFIO_TX_T30n,_DIFFOUT_T30n,_DQ4T,_DQ2T,_T_DQ_11,_T_DQ_11)_C14") (pintype "bidirectional"))
    )
    (net (code "88") (name "/ddr1_dq12") (class "Default")
      (node (ref "D4") (pin "F18") (pinfunction "IO,_(DIFFIO_RX_T27n,_DIFFOUT_T27n,_DQ4T,_DQ2T,_T_DQ_12,_T_DQ_12)_F18") (pintype "bidirectional"))
    )
    (net (code "89") (name "/ddr1_dq13") (class "Default")
      (node (ref "D4") (pin "G18") (pinfunction "IO,_(DIFFIO_RX_T27p,_DIFFOUT_T27p,_DQ4T,_DQ2T,_T_DQ_13,_T_DQ_13)_G18") (pintype "bidirectional"))
    )
    (net (code "90") (name "/ddr1_dq14") (class "Default")
      (node (ref "D4") (pin "B18") (pinfunction "IO,_(DIFFIO_TX_T28p,_DIFFOUT_T28p,_DQ4T,_DQ2T,_T_DQ_14,_T_DQ_14)_B18") (pintype "bidirectional"))
    )
    (net (code "91") (name "/ddr1_dq15") (class "Default")
      (node (ref "D4") (pin "A19") (pinfunction "IO,_(DIFFIO_TX_T26n,_DIFFOUT_T26n,_DQ4T,_DQ2T,_T_DQ_15,_T_DQ_15)_A19") (pintype "bidirectional"))
    )
    (net (code "92") (name "/ddr1_dqs0_n") (class "Default")
      (node (ref "D4") (pin "J17") (pinfunction "IO,_(DIFFIO_RX_T37n,_DIFFOUT_T37n,_DQSn5T,__,_T_DQS#_0,_T_DQS#_0)_J17") (pintype "bidirectional"))
    )
    (net (code "93") (name "/ddr1_dqs0_p") (class "Default")
      (node (ref "D4") (pin "K17") (pinfunction "IO,_(DIFFIO_RX_T37p,_DIFFOUT_T37p,_DQS5T,__,_T_DQS_0,_T_DQS_0)_K17") (pintype "bidirectional"))
    )
    (net (code "94") (name "/ddr1_dqs1_n") (class "Default")
      (node (ref "D4") (pin "L16") (pinfunction "IO,_(DIFFIO_RX_T29n,_DIFFOUT_T29n,_DQSn4T,_DQ2T,_T_DQS#_1,_T_DQS#_1)_L16") (pintype "bidirectional"))
    )
    (net (code "95") (name "/ddr1_dqs1_p") (class "Default")
      (node (ref "D4") (pin "K16") (pinfunction "IO,_(DIFFIO_RX_T29p,_DIFFOUT_T29p,_DQS4T,_DQ2T,_T_DQS_1,_T_DQS_1)_K16") (pintype "bidirectional"))
    )
    (net (code "96") (name "/ddr1_odt") (class "Default")
      (node (ref "D4") (pin "B13") (pinfunction "IO,_(DIFFIO_TX_T38p,_DIFFOUT_T38p,__,__,_T_ODT_0,_T_ODT_0)_B13") (pintype "bidirectional"))
    )
    (net (code "97") (name "/ddr1_ras") (class "Default")
      (node (ref "D4") (pin "B8") (pinfunction "IO,_(DIFFIO_TX_T50n,_DIFFOUT_T50n,_DQ7T,__,_T_RAS#)_B8") (pintype "bidirectional"))
    )
    (net (code "98") (name "/ddr1_reset_n") (class "Default")
      (node (ref "D4") (pin "B22") (pinfunction "IO,_(DIFFIO_TX_T22p,_DIFFOUT_T22p,__,__,_T_RESET#,_T_RESET#)_B22") (pintype "bidirectional"))
    )
    (net (code "99") (name "/ddr1_we") (class "Default")
      (node (ref "D4") (pin "C7") (pinfunction "IO,_(DIFFIO_TX_T56p,_DIFFOUT_T56p,_DQ7T,__,_T_WE#)_C7") (pintype "bidirectional"))
    )
    (net (code "100") (name "Net-(D4C-IO,_RZQ_0,_(DIFFIO_TX_B41n,_DIFFOUT_B41n))") (class "Default")
      (node (ref "D4") (pin "AK13") (pinfunction "IO,_RZQ_0,_(DIFFIO_TX_B41n,_DIFFOUT_B41n)_AK13") (pintype "bidirectional"))
      (node (ref "R24") (pin "1") (pinfunction "1_1") (pintype "passive"))
    )
    (net (code "101") (name "Net-(D4G-IO,_RZQ_2,_(DIFFIO_TX_T40n,_DIFFOUT_T40n))") (class "Default")
      (node (ref "D4") (pin "B12") (pinfunction "IO,_RZQ_2,_(DIFFIO_TX_T40n,_DIFFOUT_T40n)_B12") (pintype "bidirectional"))
      (node (ref "R23") (pin "1") (pinfunction "1_1") (pintype "passive"))
    )
    (net (code "102") (name "unconnected-(D4B-IO,_(DIFFIO_RX_B18n,_DIFFOUT_B18n,_DQ3B,_DQ1B)-PadAD13)") (class "Default")
      (node (ref "D4") (pin "AD13") (pinfunction "IO,_(DIFFIO_RX_B18n,_DIFFOUT_B18n,_DQ3B,_DQ1B)_AD13") (pintype "bidirectional"))
    )
    (net (code "103") (name "unconnected-(D4B-IO,_(DIFFIO_RX_B18p,_DIFFOUT_B18p,_DQ3B,_DQ1B)-PadAD12)") (class "Default")
      (node (ref "D4") (pin "AD12") (pinfunction "IO,_(DIFFIO_RX_B18p,_DIFFOUT_B18p,_DQ3B,_DQ1B)_AD12") (pintype "bidirectional"))
    )
    (net (code "104") (name "unconnected-(D4B-IO,_(DIFFIO_RX_B19n,_DIFFOUT_B19n,_DQSn3B,_DQ1B)-PadW12)") (class "Default")
      (node (ref "D4") (pin "W12") (pinfunction "IO,_(DIFFIO_RX_B19n,_DIFFOUT_B19n,_DQSn3B,_DQ1B)_W12") (pintype "bidirectional"))
    )
    (net (code "105") (name "unconnected-(D4B-IO,_(DIFFIO_RX_B19p,_DIFFOUT_B19p,_DQS3B,_DQ1B)-PadV12)") (class "Default")
      (node (ref "D4") (pin "V12") (pinfunction "IO,_(DIFFIO_RX_B19p,_DIFFOUT_B19p,_DQS3B,_DQ1B)_V12") (pintype "bidirectional"))
    )
    (net (code "106") (name "unconnected-(D4B-IO,_(DIFFIO_RX_B22n,_DIFFOUT_B22n,_DQ3B,_DQ1B)-PadAE13)") (class "Default")
      (node (ref "D4") (pin "AE13") (pinfunction "IO,_(DIFFIO_RX_B22n,_DIFFOUT_B22n,_DQ3B,_DQ1B)_AE13") (pintype "bidirectional"))
    )
    (net (code "107") (name "unconnected-(D4B-IO,_(DIFFIO_RX_B22p,_DIFFOUT_B22p,_DQ3B,_DQ1B)-PadAE12)") (class "Default")
      (node (ref "D4") (pin "AE12") (pinfunction "IO,_(DIFFIO_RX_B22p,_DIFFOUT_B22p,_DQ3B,_DQ1B)_AE12") (pintype "bidirectional"))
    )
    (net (code "108") (name "unconnected-(D4B-IO,_(DIFFIO_RX_B23n,_DIFFOUT_B23n)-PadAB13)") (class "Default")
      (node (ref "D4") (pin "AB13") (pinfunction "IO,_(DIFFIO_RX_B23n,_DIFFOUT_B23n)_AB13") (pintype "bidirectional"))
    )
    (net (code "109") (name "unconnected-(D4B-IO,_(DIFFIO_RX_B23p,_DIFFOUT_B23p)-PadAB12)") (class "Default")
      (node (ref "D4") (pin "AB12") (pinfunction "IO,_(DIFFIO_RX_B23p,_DIFFOUT_B23p)_AB12") (pintype "bidirectional"))
    )
    (net (code "110") (name "unconnected-(D4B-IO,_(DIFFIO_RX_B26n,_DIFFOUT_B26n,_DQ4B,_DQ1B,_B_A_15)-PadAG12)") (class "Default")
      (node (ref "D4") (pin "AG12") (pinfunction "IO,_(DIFFIO_RX_B26n,_DIFFOUT_B26n,_DQ4B,_DQ1B,_B_A_15)_AG12") (pintype "bidirectional"))
    )
    (net (code "111") (name "unconnected-(D4B-IO,_(DIFFIO_RX_B27n,_DIFFOUT_B27n,_DQSn4B,_DQSn1B,_B_CS#_1,_B_CS#_1)-PadAA13)") (class "Default")
      (node (ref "D4") (pin "AA13") (pinfunction "IO,_(DIFFIO_RX_B27n,_DIFFOUT_B27n,_DQSn4B,_DQSn1B,_B_CS#_1,_B_CS#_1)_AA13") (pintype "bidirectional"))
    )
    (net (code "112") (name "unconnected-(D4B-IO,_(DIFFIO_TX_B17n,_DIFFOUT_B17n)-PadAF10)") (class "Default")
      (node (ref "D4") (pin "AF10") (pinfunction "IO,_(DIFFIO_TX_B17n,_DIFFOUT_B17n)_AF10") (pintype "bidirectional"))
    )
    (net (code "113") (name "unconnected-(D4B-IO,_(DIFFIO_TX_B17p,_DIFFOUT_B17p,_DQ3B,_DQ1B)-PadAE10)") (class "Default")
      (node (ref "D4") (pin "AE10") (pinfunction "IO,_(DIFFIO_TX_B17p,_DIFFOUT_B17p,_DQ3B,_DQ1B)_AE10") (pintype "bidirectional"))
    )
    (net (code "114") (name "unconnected-(D4B-IO,_(DIFFIO_TX_B20n,_DIFFOUT_B20n,_DQ3B,_DQ1B)-PadAJ2)") (class "Default")
      (node (ref "D4") (pin "AJ2") (pinfunction "IO,_(DIFFIO_TX_B20n,_DIFFOUT_B20n,_DQ3B,_DQ1B)_AJ2") (pintype "bidirectional"))
    )
    (net (code "115") (name "unconnected-(D4B-IO,_(DIFFIO_TX_B20p,_DIFFOUT_B20p)-PadAJ1)") (class "Default")
      (node (ref "D4") (pin "AJ1") (pinfunction "IO,_(DIFFIO_TX_B20p,_DIFFOUT_B20p)_AJ1") (pintype "bidirectional"))
    )
    (net (code "116") (name "unconnected-(D4B-IO,_(DIFFIO_TX_B21n,_DIFFOUT_B21n,_DQ3B,_DQ1B)-PadAK3)") (class "Default")
      (node (ref "D4") (pin "AK3") (pinfunction "IO,_(DIFFIO_TX_B21n,_DIFFOUT_B21n,_DQ3B,_DQ1B)_AK3") (pintype "bidirectional"))
    )
    (net (code "117") (name "unconnected-(D4B-IO,_(DIFFIO_TX_B21p,_DIFFOUT_B21p,_DQ3B,_DQ1B)-PadAJ3)") (class "Default")
      (node (ref "D4") (pin "AJ3") (pinfunction "IO,_(DIFFIO_TX_B21p,_DIFFOUT_B21p,_DQ3B,_DQ1B)_AJ3") (pintype "bidirectional"))
    )
    (net (code "118") (name "unconnected-(D4B-IO,_(DIFFIO_TX_B24n,_DIFFOUT_B24n,_DQ3B,_DQ1B)-PadAJ5)") (class "Default")
      (node (ref "D4") (pin "AJ5") (pinfunction "IO,_(DIFFIO_TX_B24n,_DIFFOUT_B24n,_DQ3B,_DQ1B)_AJ5") (pintype "bidirectional"))
    )
    (net (code "119") (name "unconnected-(D4B-IO,_(DIFFIO_TX_B24p,_DIFFOUT_B24p,_DQ3B,_DQ1B)-PadAJ4)") (class "Default")
      (node (ref "D4") (pin "AJ4") (pinfunction "IO,_(DIFFIO_TX_B24p,_DIFFOUT_B24p,_DQ3B,_DQ1B)_AJ4") (pintype "bidirectional"))
    )
    (net (code "120") (name "unconnected-(D4B-IO,_CLK0n,_FPLL_BL_FBn,_(DIFFIO_RX_B31n,_DIFFOUT_B31n)-PadAC14)") (class "Default")
      (node (ref "D4") (pin "AC14") (pinfunction "IO,_CLK0n,_FPLL_BL_FBn,_(DIFFIO_RX_B31n,_DIFFOUT_B31n)_AC14") (pintype "bidirectional"))
    )
    (net (code "121") (name "unconnected-(D4B-IO,_CLK0p,_FPLL_BL_FBp,_(DIFFIO_RX_B31p,_DIFFOUT_B31p)-PadAB14)") (class "Default")
      (node (ref "D4") (pin "AB14") (pinfunction "IO,_CLK0p,_FPLL_BL_FBp,_(DIFFIO_RX_B31p,_DIFFOUT_B31p)_AB14") (pintype "bidirectional"))
    )
    (net (code "122") (name "unconnected-(D4B-IO,_CLK1n,_(DIFFIO_RX_B39n,_DIFFOUT_B39n)-PadAA15)") (class "Default")
      (node (ref "D4") (pin "AA15") (pinfunction "IO,_CLK1n,_(DIFFIO_RX_B39n,_DIFFOUT_B39n)_AA15") (pintype "bidirectional"))
    )
    (net (code "123") (name "unconnected-(D4B-IO,_CLK1p,_(DIFFIO_RX_B39p,_DIFFOUT_B39p)-PadY15)") (class "Default")
      (node (ref "D4") (pin "Y15") (pinfunction "IO,_CLK1p,_(DIFFIO_RX_B39p,_DIFFOUT_B39p)_Y15") (pintype "bidirectional"))
    )
    (net (code "124") (name "unconnected-(D4C-IO,_(DIFFIO_RX_B58n,_DIFFOUT_B58n,_DQ8B,_DQ2B,_B_DQ_16,_B_DQ_16)-PadAE18)") (class "Default")
      (node (ref "D4") (pin "AE18") (pinfunction "IO,_(DIFFIO_RX_B58n,_DIFFOUT_B58n,_DQ8B,_DQ2B,_B_DQ_16,_B_DQ_16)_AE18") (pintype "bidirectional"))
    )
    (net (code "125") (name "unconnected-(D4C-IO,_(DIFFIO_RX_B58p,_DIFFOUT_B58p,_DQ8B,_DQ2B,_B_DQ_17,_B_DQ_17)-PadAD18)") (class "Default")
      (node (ref "D4") (pin "AD18") (pinfunction "IO,_(DIFFIO_RX_B58p,_DIFFOUT_B58p,_DQ8B,_DQ2B,_B_DQ_17,_B_DQ_17)_AD18") (pintype "bidirectional"))
    )
    (net (code "126") (name "unconnected-(D4C-IO,_(DIFFIO_RX_B59n,_DIFFOUT_B59n,_DQSn8B,_DQSn2B,_B_DQS#_2,_B_DQS#_2)-PadAA20)") (class "Default")
      (node (ref "D4") (pin "AA20") (pinfunction "IO,_(DIFFIO_RX_B59n,_DIFFOUT_B59n,_DQSn8B,_DQSn2B,_B_DQS#_2,_B_DQS#_2)_AA20") (pintype "bidirectional"))
    )
    (net (code "127") (name "unconnected-(D4C-IO,_(DIFFIO_RX_B59p,_DIFFOUT_B59p,_DQS8B,_DQS2B,_B_DQS_2,_B_DQS_2)-PadY20)") (class "Default")
      (node (ref "D4") (pin "Y20") (pinfunction "IO,_(DIFFIO_RX_B59p,_DIFFOUT_B59p,_DQS8B,_DQS2B,_B_DQS_2,_B_DQS_2)_Y20") (pintype "bidirectional"))
    )
    (net (code "128") (name "unconnected-(D4C-IO,_(DIFFIO_RX_B62n,_DIFFOUT_B62n,_DQ8B,_DQ2B,_B_DQ_20,_B_DQ_20)-PadAF19)") (class "Default")
      (node (ref "D4") (pin "AF19") (pinfunction "IO,_(DIFFIO_RX_B62n,_DIFFOUT_B62n,_DQ8B,_DQ2B,_B_DQ_20,_B_DQ_20)_AF19") (pintype "bidirectional"))
    )
    (net (code "129") (name "unconnected-(D4C-IO,_(DIFFIO_RX_B62p,_DIFFOUT_B62p,_DQ8B,_DQ2B,_B_DQ_21,_B_DQ_21)-PadAF18)") (class "Default")
      (node (ref "D4") (pin "AF18") (pinfunction "IO,_(DIFFIO_RX_B62p,_DIFFOUT_B62p,_DQ8B,_DQ2B,_B_DQ_21,_B_DQ_21)_AF18") (pintype "bidirectional"))
    )
    (net (code "130") (name "unconnected-(D4C-IO,_(DIFFIO_RX_B66n,_DIFFOUT_B66n,_DQ9B,_DQ3B,_B_DQ_24,_B_DQ_24)-PadAG19)") (class "Default")
      (node (ref "D4") (pin "AG19") (pinfunction "IO,_(DIFFIO_RX_B66n,_DIFFOUT_B66n,_DQ9B,_DQ3B,_B_DQ_24,_B_DQ_24)_AG19") (pintype "bidirectional"))
    )
    (net (code "131") (name "unconnected-(D4C-IO,_(DIFFIO_RX_B66p,_DIFFOUT_B66p,_DQ9B,_DQ3B,_B_DQ_25,_B_DQ_25)-PadAG18)") (class "Default")
      (node (ref "D4") (pin "AG18") (pinfunction "IO,_(DIFFIO_RX_B66p,_DIFFOUT_B66p,_DQ9B,_DQ3B,_B_DQ_25,_B_DQ_25)_AG18") (pintype "bidirectional"))
    )
    (net (code "132") (name "unconnected-(D4C-IO,_(DIFFIO_RX_B67n,_DIFFOUT_B67n,_DQSn9B,_DQ3B,_B_DQS#_3,_B_DQS#_3)-PadAC19)") (class "Default")
      (node (ref "D4") (pin "AC19") (pinfunction "IO,_(DIFFIO_RX_B67n,_DIFFOUT_B67n,_DQSn9B,_DQ3B,_B_DQS#_3,_B_DQS#_3)_AC19") (pintype "bidirectional"))
    )
    (net (code "133") (name "unconnected-(D4C-IO,_(DIFFIO_RX_B67p,_DIFFOUT_B67p,_DQS9B,_DQ3B,_B_DQS_3,_B_DQS_3)-PadAB19)") (class "Default")
      (node (ref "D4") (pin "AB19") (pinfunction "IO,_(DIFFIO_RX_B67p,_DIFFOUT_B67p,_DQS9B,_DQ3B,_B_DQS_3,_B_DQS_3)_AB19") (pintype "bidirectional"))
    )
    (net (code "134") (name "unconnected-(D4C-IO,_(DIFFIO_RX_B70n,_DIFFOUT_B70n,_DQ9B,_DQ3B,_B_DQ_28,_B_DQ_28)-PadAE20)") (class "Default")
      (node (ref "D4") (pin "AE20") (pinfunction "IO,_(DIFFIO_RX_B70n,_DIFFOUT_B70n,_DQ9B,_DQ3B,_B_DQ_28,_B_DQ_28)_AE20") (pintype "bidirectional"))
    )
    (net (code "135") (name "unconnected-(D4C-IO,_(DIFFIO_RX_B70p,_DIFFOUT_B70p,_DQ9B,_DQ3B,_B_DQ_29,_B_DQ_29)-PadAD19)") (class "Default")
      (node (ref "D4") (pin "AD19") (pinfunction "IO,_(DIFFIO_RX_B70p,_DIFFOUT_B70p,_DQ9B,_DQ3B,_B_DQ_29,_B_DQ_29)_AD19") (pintype "bidirectional"))
    )
    (net (code "136") (name "unconnected-(D4C-IO,_(DIFFIO_RX_B74n,_DIFFOUT_B74n,_DQ10B,_DQ3B,_B_DQ_32,_B_DQ_32)-PadAG21)") (class "Default")
      (node (ref "D4") (pin "AG21") (pinfunction "IO,_(DIFFIO_RX_B74n,_DIFFOUT_B74n,_DQ10B,_DQ3B,_B_DQ_32,_B_DQ_32)_AG21") (pintype "bidirectional"))
    )
    (net (code "137") (name "unconnected-(D4C-IO,_(DIFFIO_RX_B74p,_DIFFOUT_B74p,_DQ10B,_DQ3B,_B_DQ_33,_B_DQ_33)-PadAF20)") (class "Default")
      (node (ref "D4") (pin "AF20") (pinfunction "IO,_(DIFFIO_RX_B74p,_DIFFOUT_B74p,_DQ10B,_DQ3B,_B_DQ_33,_B_DQ_33)_AF20") (pintype "bidirectional"))
    )
    (net (code "138") (name "unconnected-(D4C-IO,_(DIFFIO_RX_B75n,_DIFFOUT_B75n,_DQSn10B,_DQSn3B,_B_DQS#_4,_B_DQS#_4)-PadAD20)") (class "Default")
      (node (ref "D4") (pin "AD20") (pinfunction "IO,_(DIFFIO_RX_B75n,_DIFFOUT_B75n,_DQSn10B,_DQSn3B,_B_DQS#_4,_B_DQS#_4)_AD20") (pintype "bidirectional"))
    )
    (net (code "139") (name "unconnected-(D4C-IO,_(DIFFIO_RX_B75p,_DIFFOUT_B75p,_DQS10B,_DQS3B,_B_DQS_4,_B_DQS_4)-PadAC21)") (class "Default")
      (node (ref "D4") (pin "AC21") (pinfunction "IO,_(DIFFIO_RX_B75p,_DIFFOUT_B75p,_DQS10B,_DQS3B,_B_DQS_4,_B_DQS_4)_AC21") (pintype "bidirectional"))
    )
    (net (code "140") (name "unconnected-(D4C-IO,_(DIFFIO_RX_B78n,_DIFFOUT_B78n,_DQ10B,_DQ3B,_B_DQ_36,_B_DQ_36)-PadAG22)") (class "Default")
      (node (ref "D4") (pin "AG22") (pinfunction "IO,_(DIFFIO_RX_B78n,_DIFFOUT_B78n,_DQ10B,_DQ3B,_B_DQ_36,_B_DQ_36)_AG22") (pintype "bidirectional"))
    )
    (net (code "141") (name "unconnected-(D4C-IO,_(DIFFIO_RX_B78p,_DIFFOUT_B78p,_DQ10B,_DQ3B,_B_DQ_37,_B_DQ_37)-PadAF21)") (class "Default")
      (node (ref "D4") (pin "AF21") (pinfunction "IO,_(DIFFIO_RX_B78p,_DIFFOUT_B78p,_DQ10B,_DQ3B,_B_DQ_37,_B_DQ_37)_AF21") (pintype "bidirectional"))
    )
    (net (code "142") (name "unconnected-(D4C-IO,_(DIFFIO_TX_B45n,_DIFFOUT_B45n,_DQ6B,__,_B_ODT_1,_B_ODT_1)-PadAK15)") (class "Default")
      (node (ref "D4") (pin "AK15") (pinfunction "IO,_(DIFFIO_TX_B45n,_DIFFOUT_B45n,_DQ6B,__,_B_ODT_1,_B_ODT_1)_AK15") (pintype "bidirectional"))
    )
    (net (code "143") (name "unconnected-(D4C-IO,_(DIFFIO_TX_B52p,_DIFFOUT_B52p,__,__,_B_CKE_1,_B_CKE_1)-PadAJ17)") (class "Default")
      (node (ref "D4") (pin "AJ17") (pinfunction "IO,_(DIFFIO_TX_B52p,_DIFFOUT_B52p,__,__,_B_CKE_1,_B_CKE_1)_AJ17") (pintype "bidirectional"))
    )
    (net (code "144") (name "unconnected-(D4C-IO,_(DIFFIO_TX_B57p,_DIFFOUT_B57p,_DQ8B,_DQ2B,_B_DQ_18,_B_DQ_18)-PadAJ20)") (class "Default")
      (node (ref "D4") (pin "AJ20") (pinfunction "IO,_(DIFFIO_TX_B57p,_DIFFOUT_B57p,_DQ8B,_DQ2B,_B_DQ_18,_B_DQ_18)_AJ20") (pintype "bidirectional"))
    )
    (net (code "145") (name "unconnected-(D4C-IO,_(DIFFIO_TX_B60n,_DIFFOUT_B60n,_DQ8B,_DQ2B,_B_DQ_19,_B_DQ_19)-PadAK22)") (class "Default")
      (node (ref "D4") (pin "AK22") (pinfunction "IO,_(DIFFIO_TX_B60n,_DIFFOUT_B60n,_DQ8B,_DQ2B,_B_DQ_19,_B_DQ_19)_AK22") (pintype "bidirectional"))
    )
    (net (code "146") (name "unconnected-(D4C-IO,_(DIFFIO_TX_B61p,_DIFFOUT_B61p,_DQ8B,_DQ2B,_B_DQ_22,_B_DQ_22)-PadAH21)") (class "Default")
      (node (ref "D4") (pin "AH21") (pinfunction "IO,_(DIFFIO_TX_B61p,_DIFFOUT_B61p,_DQ8B,_DQ2B,_B_DQ_22,_B_DQ_22)_AH21") (pintype "bidirectional"))
    )
    (net (code "147") (name "unconnected-(D4C-IO,_(DIFFIO_TX_B64n,_DIFFOUT_B64n,_DQ8B,_DQ2B,_B_DQ_23,_B_DQ_23)-PadAK23)") (class "Default")
      (node (ref "D4") (pin "AK23") (pinfunction "IO,_(DIFFIO_TX_B64n,_DIFFOUT_B64n,_DQ8B,_DQ2B,_B_DQ_23,_B_DQ_23)_AK23") (pintype "bidirectional"))
    )
    (net (code "148") (name "unconnected-(D4C-IO,_(DIFFIO_TX_B64p,_DIFFOUT_B64p,_DQ8B,_DQ2B,_B_DM_2,_B_DM_2)-PadAJ23)") (class "Default")
      (node (ref "D4") (pin "AJ23") (pinfunction "IO,_(DIFFIO_TX_B64p,_DIFFOUT_B64p,_DQ8B,_DQ2B,_B_DM_2,_B_DM_2)_AJ23") (pintype "bidirectional"))
    )
    (net (code "149") (name "unconnected-(D4C-IO,_(DIFFIO_TX_B65p,_DIFFOUT_B65p,_DQ9B,_DQ3B,_B_DQ_26,_B_DQ_26)-PadAH24)") (class "Default")
      (node (ref "D4") (pin "AH24") (pinfunction "IO,_(DIFFIO_TX_B65p,_DIFFOUT_B65p,_DQ9B,_DQ3B,_B_DQ_26,_B_DQ_26)_AH24") (pintype "bidirectional"))
    )
    (net (code "150") (name "unconnected-(D4C-IO,_(DIFFIO_TX_B68n,_DIFFOUT_B68n,_DQ9B,_DQ3B,_B_DQ_27,_B_DQ_27)-PadAK25)") (class "Default")
      (node (ref "D4") (pin "AK25") (pinfunction "IO,_(DIFFIO_TX_B68n,_DIFFOUT_B68n,_DQ9B,_DQ3B,_B_DQ_27,_B_DQ_27)_AK25") (pintype "bidirectional"))
    )
    (net (code "151") (name "unconnected-(D4C-IO,_(DIFFIO_TX_B69p,_DIFFOUT_B69p,_DQ9B,_DQ3B,_B_DQ_30,_B_DQ_30)-PadAG24)") (class "Default")
      (node (ref "D4") (pin "AG24") (pinfunction "IO,_(DIFFIO_TX_B69p,_DIFFOUT_B69p,_DQ9B,_DQ3B,_B_DQ_30,_B_DQ_30)_AG24") (pintype "bidirectional"))
    )
    (net (code "152") (name "unconnected-(D4C-IO,_(DIFFIO_TX_B72n,_DIFFOUT_B72n,_DQ9B,_DQ3B,_B_DQ_31,_B_DQ_31)-PadAK26)") (class "Default")
      (node (ref "D4") (pin "AK26") (pinfunction "IO,_(DIFFIO_TX_B72n,_DIFFOUT_B72n,_DQ9B,_DQ3B,_B_DQ_31,_B_DQ_31)_AK26") (pintype "bidirectional"))
    )
    (net (code "153") (name "unconnected-(D4C-IO,_(DIFFIO_TX_B72p,_DIFFOUT_B72p,_DQ9B,_DQ3B,_B_DM_3,_B_DM_3)-PadAJ27)") (class "Default")
      (node (ref "D4") (pin "AJ27") (pinfunction "IO,_(DIFFIO_TX_B72p,_DIFFOUT_B72p,_DQ9B,_DQ3B,_B_DM_3,_B_DM_3)_AJ27") (pintype "bidirectional"))
    )
    (net (code "154") (name "unconnected-(D4C-IO,_(DIFFIO_TX_B73p,_DIFFOUT_B73p,_DQ10B,_DQ3B,_B_DQ_34,_B_DQ_34)-PadAK27)") (class "Default")
      (node (ref "D4") (pin "AK27") (pinfunction "IO,_(DIFFIO_TX_B73p,_DIFFOUT_B73p,_DQ10B,_DQ3B,_B_DQ_34,_B_DQ_34)_AK27") (pintype "bidirectional"))
    )
    (net (code "155") (name "unconnected-(D4C-IO,_(DIFFIO_TX_B76n,_DIFFOUT_B76n,_DQ10B,_DQ3B,_B_DQ_35,_B_DQ_35)-PadAH26)") (class "Default")
      (node (ref "D4") (pin "AH26") (pinfunction "IO,_(DIFFIO_TX_B76n,_DIFFOUT_B76n,_DQ10B,_DQ3B,_B_DQ_35,_B_DQ_35)_AH26") (pintype "bidirectional"))
    )
    (net (code "156") (name "unconnected-(D4C-IO,_(DIFFIO_TX_B77p,_DIFFOUT_B77p,_DQ10B,_DQ3B,_B_DQ_38,_B_DQ_38)-PadAE22)") (class "Default")
      (node (ref "D4") (pin "AE22") (pinfunction "IO,_(DIFFIO_TX_B77p,_DIFFOUT_B77p,_DQ10B,_DQ3B,_B_DQ_38,_B_DQ_38)_AE22") (pintype "bidirectional"))
    )
    (net (code "157") (name "unconnected-(D4C-IO,_(DIFFIO_TX_B80n,_DIFFOUT_B80n,_DQ10B,_DQ3B,_B_DQ_39,_B_DQ_39)-PadAH22)") (class "Default")
      (node (ref "D4") (pin "AH22") (pinfunction "IO,_(DIFFIO_TX_B80n,_DIFFOUT_B80n,_DQ10B,_DQ3B,_B_DQ_39,_B_DQ_39)_AH22") (pintype "bidirectional"))
    )
    (net (code "158") (name "unconnected-(D4C-IO,_(DIFFIO_TX_B80p,_DIFFOUT_B80p,_DQ10B,_DQ3B,_B_DM_4,_B_DM_4)-PadAG23)") (class "Default")
      (node (ref "D4") (pin "AG23") (pinfunction "IO,_(DIFFIO_TX_B80p,_DIFFOUT_B80p,_DQ10B,_DQ3B,_B_DM_4,_B_DM_4)_AG23") (pintype "bidirectional"))
    )
    (net (code "159") (name "unconnected-(D4C-IO,_CLK2n,_(DIFFIO_RX_B47n,_DIFFOUT_B47n)-PadAC15)") (class "Default")
      (node (ref "D4") (pin "AC15") (pinfunction "IO,_CLK2n,_(DIFFIO_RX_B47n,_DIFFOUT_B47n)_AC15") (pintype "bidirectional"))
    )
    (net (code "160") (name "unconnected-(D4C-IO,_CLK2p,_(DIFFIO_RX_B47p,_DIFFOUT_B47p)-PadAB16)") (class "Default")
      (node (ref "D4") (pin "AB16") (pinfunction "IO,_CLK2p,_(DIFFIO_RX_B47p,_DIFFOUT_B47p)_AB16") (pintype "bidirectional"))
    )
    (net (code "161") (name "unconnected-(D4C-IO,_CLK3n,_(DIFFIO_RX_B55n,_DIFFOUT_B55n)-PadAB18)") (class "Default")
      (node (ref "D4") (pin "AB18") (pinfunction "IO,_CLK3n,_(DIFFIO_RX_B55n,_DIFFOUT_B55n)_AB18") (pintype "bidirectional"))
    )
    (net (code "162") (name "unconnected-(D4C-IO,_CLK3p,_(DIFFIO_RX_B55p,_DIFFOUT_B55p)-PadAB17)") (class "Default")
      (node (ref "D4") (pin "AB17") (pinfunction "IO,_CLK3p,_(DIFFIO_RX_B55p,_DIFFOUT_B55p)_AB17") (pintype "bidirectional"))
    )
    (net (code "163") (name "unconnected-(D4G-IO,_(DIFFIO_RX_T3n,_DIFFOUT_T3n,_DQ1T,_DQ1T,_T_DQ_36,_T_DQ_36)-PadG23)") (class "Default")
      (node (ref "D4") (pin "G23") (pinfunction "IO,_(DIFFIO_RX_T3n,_DIFFOUT_T3n,_DQ1T,_DQ1T,_T_DQ_36,_T_DQ_36)_G23") (pintype "bidirectional"))
    )
    (net (code "164") (name "unconnected-(D4G-IO,_(DIFFIO_RX_T3p,_DIFFOUT_T3p,_DQ1T,_DQ1T,_T_DQ_37,_T_DQ_37)-PadG22)") (class "Default")
      (node (ref "D4") (pin "G22") (pinfunction "IO,_(DIFFIO_RX_T3p,_DIFFOUT_T3p,_DQ1T,_DQ1T,_T_DQ_37,_T_DQ_37)_G22") (pintype "bidirectional"))
    )
    (net (code "165") (name "unconnected-(D4G-IO,_(DIFFIO_RX_T5n,_DIFFOUT_T5n,_DQSn1T,_DQSn1T,_T_DQS#_4,_T_DQS#_4)-PadL19)") (class "Default")
      (node (ref "D4") (pin "L19") (pinfunction "IO,_(DIFFIO_RX_T5n,_DIFFOUT_T5n,_DQSn1T,_DQSn1T,_T_DQS#_4,_T_DQS#_4)_L19") (pintype "bidirectional"))
    )
    (net (code "166") (name "unconnected-(D4G-IO,_(DIFFIO_RX_T5p,_DIFFOUT_T5p,_DQS1T,_DQS1T,_T_DQS_4,_T_DQS_4)-PadL20)") (class "Default")
      (node (ref "D4") (pin "L20") (pinfunction "IO,_(DIFFIO_RX_T5p,_DIFFOUT_T5p,_DQS1T,_DQS1T,_T_DQS_4,_T_DQS_4)_L20") (pintype "bidirectional"))
    )
    (net (code "167") (name "unconnected-(D4G-IO,_(DIFFIO_RX_T7n,_DIFFOUT_T7n,_DQ1T,_DQ1T,_T_DQ_32,_T_DQ_32)-PadE21)") (class "Default")
      (node (ref "D4") (pin "E21") (pinfunction "IO,_(DIFFIO_RX_T7n,_DIFFOUT_T7n,_DQ1T,_DQ1T,_T_DQ_32,_T_DQ_32)_E21") (pintype "bidirectional"))
    )
    (net (code "168") (name "unconnected-(D4G-IO,_(DIFFIO_RX_T7p,_DIFFOUT_T7p,_DQ1T,_DQ1T,_T_DQ_33,_T_DQ_33)-PadE22)") (class "Default")
      (node (ref "D4") (pin "E22") (pinfunction "IO,_(DIFFIO_RX_T7p,_DIFFOUT_T7p,_DQ1T,_DQ1T,_T_DQ_33,_T_DQ_33)_E22") (pintype "bidirectional"))
    )
    (net (code "169") (name "unconnected-(D4G-IO,_(DIFFIO_RX_T11n,_DIFFOUT_T11n,_DQ2T,_DQ1T,_T_DQ_28,_T_DQ_28)-PadC20)") (class "Default")
      (node (ref "D4") (pin "C20") (pinfunction "IO,_(DIFFIO_RX_T11n,_DIFFOUT_T11n,_DQ2T,_DQ1T,_T_DQ_28,_T_DQ_28)_C20") (pintype "bidirectional"))
    )
    (net (code "170") (name "unconnected-(D4G-IO,_(DIFFIO_RX_T11p,_DIFFOUT_T11p,_DQ2T,_DQ1T,_T_DQ_29,_T_DQ_29)-PadC21)") (class "Default")
      (node (ref "D4") (pin "C21") (pinfunction "IO,_(DIFFIO_RX_T11p,_DIFFOUT_T11p,_DQ2T,_DQ1T,_T_DQ_29,_T_DQ_29)_C21") (pintype "bidirectional"))
    )
    (net (code "171") (name "unconnected-(D4G-IO,_(DIFFIO_RX_T13n,_DIFFOUT_T13n,_DQSn2T,_DQ1T,_T_DQS#_3,_T_DQS#_3)-PadJ19)") (class "Default")
      (node (ref "D4") (pin "J19") (pinfunction "IO,_(DIFFIO_RX_T13n,_DIFFOUT_T13n,_DQSn2T,_DQ1T,_T_DQS#_3,_T_DQS#_3)_J19") (pintype "bidirectional"))
    )
    (net (code "172") (name "unconnected-(D4G-IO,_(DIFFIO_RX_T13p,_DIFFOUT_T13p,_DQS2T,_DQ1T,_T_DQS_3,_T_DQS_3)-PadK20)") (class "Default")
      (node (ref "D4") (pin "K20") (pinfunction "IO,_(DIFFIO_RX_T13p,_DIFFOUT_T13p,_DQS2T,_DQ1T,_T_DQS_3,_T_DQS_3)_K20") (pintype "bidirectional"))
    )
    (net (code "173") (name "unconnected-(D4G-IO,_(DIFFIO_RX_T15n,_DIFFOUT_T15n,_DQ2T,_DQ1T,_T_DQ_24,_T_DQ_24)-PadC19)") (class "Default")
      (node (ref "D4") (pin "C19") (pinfunction "IO,_(DIFFIO_RX_T15n,_DIFFOUT_T15n,_DQ2T,_DQ1T,_T_DQ_24,_T_DQ_24)_C19") (pintype "bidirectional"))
    )
    (net (code "174") (name "unconnected-(D4G-IO,_(DIFFIO_RX_T15p,_DIFFOUT_T15p,_DQ2T,_DQ1T,_T_DQ_25,_T_DQ_25)-PadD20)") (class "Default")
      (node (ref "D4") (pin "D20") (pinfunction "IO,_(DIFFIO_RX_T15p,_DIFFOUT_T15p,_DQ2T,_DQ1T,_T_DQ_25,_T_DQ_25)_D20") (pintype "bidirectional"))
    )
    (net (code "175") (name "unconnected-(D4G-IO,_(DIFFIO_RX_T19n,_DIFFOUT_T19n,_DQ3T,_DQ2T,_T_DQ_20,_T_DQ_20)-PadE18)") (class "Default")
      (node (ref "D4") (pin "E18") (pinfunction "IO,_(DIFFIO_RX_T19n,_DIFFOUT_T19n,_DQ3T,_DQ2T,_T_DQ_20,_T_DQ_20)_E18") (pintype "bidirectional"))
    )
    (net (code "176") (name "unconnected-(D4G-IO,_(DIFFIO_RX_T19p,_DIFFOUT_T19p,_DQ3T,_DQ2T,_T_DQ_21,_T_DQ_21)-PadF19)") (class "Default")
      (node (ref "D4") (pin "F19") (pinfunction "IO,_(DIFFIO_RX_T19p,_DIFFOUT_T19p,_DQ3T,_DQ2T,_T_DQ_21,_T_DQ_21)_F19") (pintype "bidirectional"))
    )
    (net (code "177") (name "unconnected-(D4G-IO,_(DIFFIO_RX_T21n,_DIFFOUT_T21n,_DQSn3T,_DQSn2T,_T_DQS#_2,_T_DQS#_2)-PadK18)") (class "Default")
      (node (ref "D4") (pin "K18") (pinfunction "IO,_(DIFFIO_RX_T21n,_DIFFOUT_T21n,_DQSn3T,_DQSn2T,_T_DQS#_2,_T_DQS#_2)_K18") (pintype "bidirectional"))
    )
    (net (code "178") (name "unconnected-(D4G-IO,_(DIFFIO_RX_T21p,_DIFFOUT_T21p,_DQS3T,_DQS2T,_T_DQS_2,_T_DQS_2)-PadL18)") (class "Default")
      (node (ref "D4") (pin "L18") (pinfunction "IO,_(DIFFIO_RX_T21p,_DIFFOUT_T21p,_DQS3T,_DQS2T,_T_DQS_2,_T_DQS_2)_L18") (pintype "bidirectional"))
    )
    (net (code "179") (name "unconnected-(D4G-IO,_(DIFFIO_RX_T23n,_DIFFOUT_T23n,_DQ3T,_DQ2T,_T_DQ_16,_T_DQ_16)-PadD18)") (class "Default")
      (node (ref "D4") (pin "D18") (pinfunction "IO,_(DIFFIO_RX_T23n,_DIFFOUT_T23n,_DQ3T,_DQ2T,_T_DQ_16,_T_DQ_16)_D18") (pintype "bidirectional"))
    )
    (net (code "180") (name "unconnected-(D4G-IO,_(DIFFIO_RX_T23p,_DIFFOUT_T23p,_DQ3T,_DQ2T,_T_DQ_17,_T_DQ_17)-PadD19)") (class "Default")
      (node (ref "D4") (pin "D19") (pinfunction "IO,_(DIFFIO_RX_T23p,_DIFFOUT_T23p,_DQ3T,_DQ2T,_T_DQ_17,_T_DQ_17)_D19") (pintype "bidirectional"))
    )
    (net (code "181") (name "unconnected-(D4G-IO,_(DIFFIO_TX_T2n,_DIFFOUT_T2n,_DQ1T,_DQ1T,_T_DQ_39,_T_DQ_39)-PadE25)") (class "Default")
      (node (ref "D4") (pin "E25") (pinfunction "IO,_(DIFFIO_TX_T2n,_DIFFOUT_T2n,_DQ1T,_DQ1T,_T_DQ_39,_T_DQ_39)_E25") (pintype "bidirectional"))
    )
    (net (code "182") (name "unconnected-(D4G-IO,_(DIFFIO_TX_T2p,_DIFFOUT_T2p,_DQ1T,_DQ1T,_T_DM_4,_T_DM_4)-PadE26)") (class "Default")
      (node (ref "D4") (pin "E26") (pinfunction "IO,_(DIFFIO_TX_T2p,_DIFFOUT_T2p,_DQ1T,_DQ1T,_T_DM_4,_T_DM_4)_E26") (pintype "bidirectional"))
    )
    (net (code "183") (name "unconnected-(D4G-IO,_(DIFFIO_TX_T4p,_DIFFOUT_T4p,_DQ1T,_DQ1T,_T_DQ_38,_T_DQ_38)-PadC27)") (class "Default")
      (node (ref "D4") (pin "C27") (pinfunction "IO,_(DIFFIO_TX_T4p,_DIFFOUT_T4p,_DQ1T,_DQ1T,_T_DQ_38,_T_DQ_38)_C27") (pintype "bidirectional"))
    )
    (net (code "184") (name "unconnected-(D4G-IO,_(DIFFIO_TX_T6n,_DIFFOUT_T6n,_DQ1T,_DQ1T,_T_DQ_35,_T_DQ_35)-PadA28)") (class "Default")
      (node (ref "D4") (pin "A28") (pinfunction "IO,_(DIFFIO_TX_T6n,_DIFFOUT_T6n,_DQ1T,_DQ1T,_T_DQ_35,_T_DQ_35)_A28") (pintype "bidirectional"))
    )
    (net (code "185") (name "unconnected-(D4G-IO,_(DIFFIO_TX_T8p,_DIFFOUT_T8p,_DQ1T,_DQ1T,_T_DQ_34,_T_DQ_34)-PadB26)") (class "Default")
      (node (ref "D4") (pin "B26") (pinfunction "IO,_(DIFFIO_TX_T8p,_DIFFOUT_T8p,_DQ1T,_DQ1T,_T_DQ_34,_T_DQ_34)_B26") (pintype "bidirectional"))
    )
    (net (code "186") (name "unconnected-(D4G-IO,_(DIFFIO_TX_T10n,_DIFFOUT_T10n,_DQ2T,_DQ1T,_T_DQ_31,_T_DQ_31)-PadC25)") (class "Default")
      (node (ref "D4") (pin "C25") (pinfunction "IO,_(DIFFIO_TX_T10n,_DIFFOUT_T10n,_DQ2T,_DQ1T,_T_DQ_31,_T_DQ_31)_C25") (pintype "bidirectional"))
    )
    (net (code "187") (name "unconnected-(D4G-IO,_(DIFFIO_TX_T10p,_DIFFOUT_T10p,_DQ2T,_DQ1T,_T_DM_3,_T_DM_3)-PadD25)") (class "Default")
      (node (ref "D4") (pin "D25") (pinfunction "IO,_(DIFFIO_TX_T10p,_DIFFOUT_T10p,_DQ2T,_DQ1T,_T_DM_3,_T_DM_3)_D25") (pintype "bidirectional"))
    )
    (net (code "188") (name "unconnected-(D4G-IO,_(DIFFIO_TX_T12p,_DIFFOUT_T12p,_DQ2T,_DQ1T,_T_DQ_30,_T_DQ_30)-PadD23)") (class "Default")
      (node (ref "D4") (pin "D23") (pinfunction "IO,_(DIFFIO_TX_T12p,_DIFFOUT_T12p,_DQ2T,_DQ1T,_T_DQ_30,_T_DQ_30)_D23") (pintype "bidirectional"))
    )
    (net (code "189") (name "unconnected-(D4G-IO,_(DIFFIO_TX_T14n,_DIFFOUT_T14n,_DQ2T,_DQ1T,_T_DQ_27,_T_DQ_27)-PadD22)") (class "Default")
      (node (ref "D4") (pin "D22") (pinfunction "IO,_(DIFFIO_TX_T14n,_DIFFOUT_T14n,_DQ2T,_DQ1T,_T_DQ_27,_T_DQ_27)_D22") (pintype "bidirectional"))
    )
    (net (code "190") (name "unconnected-(D4G-IO,_(DIFFIO_TX_T16p,_DIFFOUT_T16p,_DQ2T,_DQ1T,_T_DQ_26,_T_DQ_26)-PadA25)") (class "Default")
      (node (ref "D4") (pin "A25") (pinfunction "IO,_(DIFFIO_TX_T16p,_DIFFOUT_T16p,_DQ2T,_DQ1T,_T_DQ_26,_T_DQ_26)_A25") (pintype "bidirectional"))
    )
    (net (code "191") (name "unconnected-(D4G-IO,_(DIFFIO_TX_T18n,_DIFFOUT_T18n,_DQ3T,_DQ2T,_T_DQ_23,_T_DQ_23)-PadB24)") (class "Default")
      (node (ref "D4") (pin "B24") (pinfunction "IO,_(DIFFIO_TX_T18n,_DIFFOUT_T18n,_DQ3T,_DQ2T,_T_DQ_23,_T_DQ_23)_B24") (pintype "bidirectional"))
    )
    (net (code "192") (name "unconnected-(D4G-IO,_(DIFFIO_TX_T18p,_DIFFOUT_T18p,_DQ3T,_DQ2T,_T_DM_2,_T_DM_2)-PadC24)") (class "Default")
      (node (ref "D4") (pin "C24") (pinfunction "IO,_(DIFFIO_TX_T18p,_DIFFOUT_T18p,_DQ3T,_DQ2T,_T_DM_2,_T_DM_2)_C24") (pintype "bidirectional"))
    )
    (net (code "193") (name "unconnected-(D4G-IO,_(DIFFIO_TX_T20p,_DIFFOUT_T20p,_DQ3T,_DQ2T,_T_DQ_22,_T_DQ_22)-PadB23)") (class "Default")
      (node (ref "D4") (pin "B23") (pinfunction "IO,_(DIFFIO_TX_T20p,_DIFFOUT_T20p,_DQ3T,_DQ2T,_T_DQ_22,_T_DQ_22)_B23") (pintype "bidirectional"))
    )
    (net (code "194") (name "unconnected-(D4G-IO,_(DIFFIO_TX_T22n,_DIFFOUT_T22n,_DQ3T,_DQ2T,_T_DQ_19,_T_DQ_19)-PadB21)") (class "Default")
      (node (ref "D4") (pin "B21") (pinfunction "IO,_(DIFFIO_TX_T22n,_DIFFOUT_T22n,_DQ3T,_DQ2T,_T_DQ_19,_T_DQ_19)_B21") (pintype "bidirectional"))
    )
    (net (code "195") (name "unconnected-(D4G-IO,_(DIFFIO_TX_T24p,_DIFFOUT_T24p,_DQ3T,_DQ2T,_T_DQ_18,_T_DQ_18)-PadA21)") (class "Default")
      (node (ref "D4") (pin "A21") (pinfunction "IO,_(DIFFIO_TX_T24p,_DIFFOUT_T24p,_DQ3T,_DQ2T,_T_DQ_18,_T_DQ_18)_A21") (pintype "bidirectional"))
    )
    (net (code "196") (name "unconnected-(D4G-IO,_(DIFFIO_TX_T30p,_DIFFOUT_T30p,__,__,_T_CKE_1,_T_CKE_1)-PadD14)") (class "Default")
      (node (ref "D4") (pin "D14") (pinfunction "IO,_(DIFFIO_TX_T30p,_DIFFOUT_T30p,__,__,_T_CKE_1,_T_CKE_1)_D14") (pintype "bidirectional"))
    )
    (net (code "197") (name "unconnected-(D4G-IO,_(DIFFIO_TX_T36n,_DIFFOUT_T36n,_DQ5T,__,_T_ODT_1,_T_ODT_1)-PadC12)") (class "Default")
      (node (ref "D4") (pin "C12") (pinfunction "IO,_(DIFFIO_TX_T36n,_DIFFOUT_T36n,_DQ5T,__,_T_ODT_1,_T_ODT_1)_C12") (pintype "bidirectional"))
    )
    (net (code "198") (name "unconnected-(D4G-IO,_CLK10n,_(DIFFIO_RX_T33n,_DIFFOUT_T33n)-PadG17)") (class "Default")
      (node (ref "D4") (pin "G17") (pinfunction "IO,_CLK10n,_(DIFFIO_RX_T33n,_DIFFOUT_T33n)_G17") (pintype "bidirectional"))
    )
    (net (code "199") (name "unconnected-(D4G-IO,_CLK10p,_(DIFFIO_RX_T33p,_DIFFOUT_T33p)-PadH17)") (class "Default")
      (node (ref "D4") (pin "H17") (pinfunction "IO,_CLK10p,_(DIFFIO_RX_T33p,_DIFFOUT_T33p)_H17") (pintype "bidirectional"))
    )
    (net (code "200") (name "unconnected-(D4G-IO,_CLK11n,_(DIFFIO_RX_T25n,_DIFFOUT_T25n)-PadJ18)") (class "Default")
      (node (ref "D4") (pin "J18") (pinfunction "IO,_CLK11n,_(DIFFIO_RX_T25n,_DIFFOUT_T25n)_J18") (pintype "bidirectional"))
    )
    (net (code "201") (name "unconnected-(D4G-IO,_CLK11p,_(DIFFIO_RX_T25p,_DIFFOUT_T25p)-PadH19)") (class "Default")
      (node (ref "D4") (pin "H19") (pinfunction "IO,_CLK11p,_(DIFFIO_RX_T25p,_DIFFOUT_T25p)_H19") (pintype "bidirectional"))
    )
    (net (code "202") (name "unconnected-(D4H-IO,_(DIFFIO_RX_T53n,_DIFFOUT_T53n,_DQSn7T,__,_T_CS#_1,_T_CS#_1)-PadH15)") (class "Default")
      (node (ref "D4") (pin "H15") (pinfunction "IO,_(DIFFIO_RX_T53n,_DIFFOUT_T53n,_DQSn7T,__,_T_CS#_1,_T_CS#_1)_H15") (pintype "bidirectional"))
    )
    (net (code "203") (name "unconnected-(D4H-IO,_(DIFFIO_RX_T55n,_DIFFOUT_T55n,_DQ7T,__,_T_A_15)-PadD10)") (class "Default")
      (node (ref "D4") (pin "D10") (pinfunction "IO,_(DIFFIO_RX_T55n,_DIFFOUT_T55n,_DQ7T,__,_T_A_15)_D10") (pintype "bidirectional"))
    )
    (net (code "204") (name "unconnected-(D4H-IO,_(DIFFIO_RX_T57n,_DIFFOUT_T57n)-PadL9)") (class "Default")
      (node (ref "D4") (pin "L9") (pinfunction "IO,_(DIFFIO_RX_T57n,_DIFFOUT_T57n)_L9") (pintype "bidirectional"))
    )
    (net (code "205") (name "unconnected-(D4H-IO,_(DIFFIO_RX_T57p,_DIFFOUT_T57p)-PadL10)") (class "Default")
      (node (ref "D4") (pin "L10") (pinfunction "IO,_(DIFFIO_RX_T57p,_DIFFOUT_T57p)_L10") (pintype "bidirectional"))
    )
    (net (code "206") (name "unconnected-(D4H-IO,_(DIFFIO_RX_T59n,_DIFFOUT_T59n,_DQ8T)-PadF14)") (class "Default")
      (node (ref "D4") (pin "F14") (pinfunction "IO,_(DIFFIO_RX_T59n,_DIFFOUT_T59n,_DQ8T)_F14") (pintype "bidirectional"))
    )
    (net (code "207") (name "unconnected-(D4H-IO,_(DIFFIO_RX_T59p,_DIFFOUT_T59p,_DQ8T)-PadG14)") (class "Default")
      (node (ref "D4") (pin "G14") (pinfunction "IO,_(DIFFIO_RX_T59p,_DIFFOUT_T59p,_DQ8T)_G14") (pintype "bidirectional"))
    )
    (net (code "208") (name "unconnected-(D4H-IO,_(DIFFIO_RX_T61n,_DIFFOUT_T61n,_DQSn8T)-PadH14)") (class "Default")
      (node (ref "D4") (pin "H14") (pinfunction "IO,_(DIFFIO_RX_T61n,_DIFFOUT_T61n,_DQSn8T)_H14") (pintype "bidirectional"))
    )
    (net (code "209") (name "unconnected-(D4H-IO,_(DIFFIO_RX_T61p,_DIFFOUT_T61p,_DQS8T)-PadJ14)") (class "Default")
      (node (ref "D4") (pin "J14") (pinfunction "IO,_(DIFFIO_RX_T61p,_DIFFOUT_T61p,_DQS8T)_J14") (pintype "bidirectional"))
    )
    (net (code "210") (name "unconnected-(D4H-IO,_(DIFFIO_RX_T63n,_DIFFOUT_T63n,_DQ8T)-PadK11)") (class "Default")
      (node (ref "D4") (pin "K11") (pinfunction "IO,_(DIFFIO_RX_T63n,_DIFFOUT_T63n,_DQ8T)_K11") (pintype "bidirectional"))
    )
    (net (code "211") (name "unconnected-(D4H-IO,_(DIFFIO_RX_T63p,_DIFFOUT_T63p,_DQ8T)-PadL11)") (class "Default")
      (node (ref "D4") (pin "L11") (pinfunction "IO,_(DIFFIO_RX_T63p,_DIFFOUT_T63p,_DQ8T)_L11") (pintype "bidirectional"))
    )
    (net (code "212") (name "unconnected-(D4H-IO,_(DIFFIO_RX_T65n,_DIFFOUT_T65n)-PadN12)") (class "Default")
      (node (ref "D4") (pin "N12") (pinfunction "IO,_(DIFFIO_RX_T65n,_DIFFOUT_T65n)_N12") (pintype "bidirectional"))
    )
    (net (code "213") (name "unconnected-(D4H-IO,_(DIFFIO_RX_T65p,_DIFFOUT_T65p)-PadP12)") (class "Default")
      (node (ref "D4") (pin "P12") (pinfunction "IO,_(DIFFIO_RX_T65p,_DIFFOUT_T65p)_P12") (pintype "bidirectional"))
    )
    (net (code "214") (name "unconnected-(D4H-IO,_(DIFFIO_RX_T67n,_DIFFOUT_T67n,_DQ9T,_DQ3T)-PadG12)") (class "Default")
      (node (ref "D4") (pin "G12") (pinfunction "IO,_(DIFFIO_RX_T67n,_DIFFOUT_T67n,_DQ9T,_DQ3T)_G12") (pintype "bidirectional"))
    )
    (net (code "215") (name "unconnected-(D4H-IO,_(DIFFIO_RX_T67p,_DIFFOUT_T67p,_DQ9T,_DQ3T)-PadH12)") (class "Default")
      (node (ref "D4") (pin "H12") (pinfunction "IO,_(DIFFIO_RX_T67p,_DIFFOUT_T67p,_DQ9T,_DQ3T)_H12") (pintype "bidirectional"))
    )
    (net (code "216") (name "unconnected-(D4H-IO,_(DIFFIO_RX_T69n,_DIFFOUT_T69n,_DQSn9T,_DQSn3T)-PadJ13)") (class "Default")
      (node (ref "D4") (pin "J13") (pinfunction "IO,_(DIFFIO_RX_T69n,_DIFFOUT_T69n,_DQSn9T,_DQSn3T)_J13") (pintype "bidirectional"))
    )
    (net (code "217") (name "unconnected-(D4H-IO,_(DIFFIO_RX_T69p,_DIFFOUT_T69p,_DQS9T,_DQS3T)-PadK13)") (class "Default")
      (node (ref "D4") (pin "K13") (pinfunction "IO,_(DIFFIO_RX_T69p,_DIFFOUT_T69p,_DQS9T,_DQS3T)_K13") (pintype "bidirectional"))
    )
    (net (code "218") (name "unconnected-(D4H-IO,_(DIFFIO_RX_T71n,_DIFFOUT_T71n,_DQ9T,_DQ3T)-PadN11)") (class "Default")
      (node (ref "D4") (pin "N11") (pinfunction "IO,_(DIFFIO_RX_T71n,_DIFFOUT_T71n,_DQ9T,_DQ3T)_N11") (pintype "bidirectional"))
    )
    (net (code "219") (name "unconnected-(D4H-IO,_(DIFFIO_RX_T71p,_DIFFOUT_T71p,_DQ9T,_DQ3T)-PadP10)") (class "Default")
      (node (ref "D4") (pin "P10") (pinfunction "IO,_(DIFFIO_RX_T71p,_DIFFOUT_T71p,_DQ9T,_DQ3T)_P10") (pintype "bidirectional"))
    )
    (net (code "220") (name "unconnected-(D4H-IO,_(DIFFIO_RX_T73n,_DIFFOUT_T73n)-PadR11)") (class "Default")
      (node (ref "D4") (pin "R11") (pinfunction "IO,_(DIFFIO_RX_T73n,_DIFFOUT_T73n)_R11") (pintype "bidirectional"))
    )
    (net (code "221") (name "unconnected-(D4H-IO,_(DIFFIO_RX_T73p,_DIFFOUT_T73p)-PadR12)") (class "Default")
      (node (ref "D4") (pin "R12") (pinfunction "IO,_(DIFFIO_RX_T73p,_DIFFOUT_T73p)_R12") (pintype "bidirectional"))
    )
    (net (code "222") (name "unconnected-(D4H-IO,_(DIFFIO_RX_T75n,_DIFFOUT_T75n,_DQ10T,_DQ3T)-PadJ12)") (class "Default")
      (node (ref "D4") (pin "J12") (pinfunction "IO,_(DIFFIO_RX_T75n,_DIFFOUT_T75n,_DQ10T,_DQ3T)_J12") (pintype "bidirectional"))
    )
    (net (code "223") (name "unconnected-(D4H-IO,_(DIFFIO_RX_T75p,_DIFFOUT_T75p,_DQ10T,_DQ3T)-PadK12)") (class "Default")
      (node (ref "D4") (pin "K12") (pinfunction "IO,_(DIFFIO_RX_T75p,_DIFFOUT_T75p,_DQ10T,_DQ3T)_K12") (pintype "bidirectional"))
    )
    (net (code "224") (name "unconnected-(D4H-IO,_(DIFFIO_RX_T77n,_DIFFOUT_T77n,_DQSn10T,_DQ3T)-PadN9)") (class "Default")
      (node (ref "D4") (pin "N9") (pinfunction "IO,_(DIFFIO_RX_T77n,_DIFFOUT_T77n,_DQSn10T,_DQ3T)_N9") (pintype "bidirectional"))
    )
    (net (code "225") (name "unconnected-(D4H-IO,_(DIFFIO_RX_T77p,_DIFFOUT_T77p,_DQS10T,_DQ3T)-PadN10)") (class "Default")
      (node (ref "D4") (pin "N10") (pinfunction "IO,_(DIFFIO_RX_T77p,_DIFFOUT_T77p,_DQS10T,_DQ3T)_N10") (pintype "bidirectional"))
    )
    (net (code "226") (name "unconnected-(D4H-IO,_(DIFFIO_RX_T79n,_DIFFOUT_T79n,_DQ10T,_DQ3T)-PadM11)") (class "Default")
      (node (ref "D4") (pin "M11") (pinfunction "IO,_(DIFFIO_RX_T79n,_DIFFOUT_T79n,_DQ10T,_DQ3T)_M11") (pintype "bidirectional"))
    )
    (net (code "227") (name "unconnected-(D4H-IO,_(DIFFIO_RX_T79p,_DIFFOUT_T79p,_DQ10T,_DQ3T)-PadM12)") (class "Default")
      (node (ref "D4") (pin "M12") (pinfunction "IO,_(DIFFIO_RX_T79p,_DIFFOUT_T79p,_DQ10T,_DQ3T)_M12") (pintype "bidirectional"))
    )
    (net (code "228") (name "unconnected-(D4H-IO,_(DIFFIO_TX_T58n,_DIFFOUT_T58n,_DQ8T)-PadE13)") (class "Default")
      (node (ref "D4") (pin "E13") (pinfunction "IO,_(DIFFIO_TX_T58n,_DIFFOUT_T58n,_DQ8T)_E13") (pintype "bidirectional"))
    )
    (net (code "229") (name "unconnected-(D4H-IO,_(DIFFIO_TX_T58p,_DIFFOUT_T58p,_DQ8T)-PadF13)") (class "Default")
      (node (ref "D4") (pin "F13") (pinfunction "IO,_(DIFFIO_TX_T58p,_DIFFOUT_T58p,_DQ8T)_F13") (pintype "bidirectional"))
    )
    (net (code "230") (name "unconnected-(D4H-IO,_(DIFFIO_TX_T60n,_DIFFOUT_T60n,_DQ8T)-PadA4)") (class "Default")
      (node (ref "D4") (pin "A4") (pinfunction "IO,_(DIFFIO_TX_T60n,_DIFFOUT_T60n,_DQ8T)_A4") (pintype "bidirectional"))
    )
    (net (code "231") (name "unconnected-(D4H-IO,_(DIFFIO_TX_T60p,_DIFFOUT_T60p,_DQ8T)-PadA5)") (class "Default")
      (node (ref "D4") (pin "A5") (pinfunction "IO,_(DIFFIO_TX_T60p,_DIFFOUT_T60p,_DQ8T)_A5") (pintype "bidirectional"))
    )
    (net (code "232") (name "unconnected-(D4H-IO,_(DIFFIO_TX_T62n,_DIFFOUT_T62n,_DQ8T)-PadH7)") (class "Default")
      (node (ref "D4") (pin "H7") (pinfunction "IO,_(DIFFIO_TX_T62n,_DIFFOUT_T62n,_DQ8T)_H7") (pintype "bidirectional"))
    )
    (net (code "233") (name "unconnected-(D4H-IO,_(DIFFIO_TX_T62p,_DIFFOUT_T62p)-PadJ7)") (class "Default")
      (node (ref "D4") (pin "J7") (pinfunction "IO,_(DIFFIO_TX_T62p,_DIFFOUT_T62p)_J7") (pintype "bidirectional"))
    )
    (net (code "234") (name "unconnected-(D4H-IO,_(DIFFIO_TX_T64n,_DIFFOUT_T64n)-PadH9)") (class "Default")
      (node (ref "D4") (pin "H9") (pinfunction "IO,_(DIFFIO_TX_T64n,_DIFFOUT_T64n)_H9") (pintype "bidirectional"))
    )
    (net (code "235") (name "unconnected-(D4H-IO,_(DIFFIO_TX_T64p,_DIFFOUT_T64p,_DQ8T)-PadJ9)") (class "Default")
      (node (ref "D4") (pin "J9") (pinfunction "IO,_(DIFFIO_TX_T64p,_DIFFOUT_T64p,_DQ8T)_J9") (pintype "bidirectional"))
    )
    (net (code "236") (name "unconnected-(D4H-IO,_(DIFFIO_TX_T66n,_DIFFOUT_T66n,_DQ9T,_DQ3T)-PadF8)") (class "Default")
      (node (ref "D4") (pin "F8") (pinfunction "IO,_(DIFFIO_TX_T66n,_DIFFOUT_T66n,_DQ9T,_DQ3T)_F8") (pintype "bidirectional"))
    )
    (net (code "237") (name "unconnected-(D4H-IO,_(DIFFIO_TX_T66p,_DIFFOUT_T66p,_DQ9T,_DQ3T)-PadG9)") (class "Default")
      (node (ref "D4") (pin "G9") (pinfunction "IO,_(DIFFIO_TX_T66p,_DIFFOUT_T66p,_DQ9T,_DQ3T)_G9") (pintype "bidirectional"))
    )
    (net (code "238") (name "unconnected-(D4H-IO,_(DIFFIO_TX_T68n,_DIFFOUT_T68n,_DQ9T,_DQ3T)-PadD8)") (class "Default")
      (node (ref "D4") (pin "D8") (pinfunction "IO,_(DIFFIO_TX_T68n,_DIFFOUT_T68n,_DQ9T,_DQ3T)_D8") (pintype "bidirectional"))
    )
    (net (code "239") (name "unconnected-(D4H-IO,_(DIFFIO_TX_T68p,_DIFFOUT_T68p,_DQ9T,_DQ3T)-PadE8)") (class "Default")
      (node (ref "D4") (pin "E8") (pinfunction "IO,_(DIFFIO_TX_T68p,_DIFFOUT_T68p,_DQ9T,_DQ3T)_E8") (pintype "bidirectional"))
    )
    (net (code "240") (name "unconnected-(D4H-IO,_(DIFFIO_TX_T70n,_DIFFOUT_T70n,_DQ9T,_DQ3T)-PadA2)") (class "Default")
      (node (ref "D4") (pin "A2") (pinfunction "IO,_(DIFFIO_TX_T70n,_DIFFOUT_T70n,_DQ9T,_DQ3T)_A2") (pintype "bidirectional"))
    )
    (net (code "241") (name "unconnected-(D4H-IO,_(DIFFIO_TX_T70p,_DIFFOUT_T70p)-PadA3)") (class "Default")
      (node (ref "D4") (pin "A3") (pinfunction "IO,_(DIFFIO_TX_T70p,_DIFFOUT_T70p)_A3") (pintype "bidirectional"))
    )
    (net (code "242") (name "unconnected-(D4H-IO,_(DIFFIO_TX_T72n,_DIFFOUT_T72n)-PadD6)") (class "Default")
      (node (ref "D4") (pin "D6") (pinfunction "IO,_(DIFFIO_TX_T72n,_DIFFOUT_T72n)_D6") (pintype "bidirectional"))
    )
    (net (code "243") (name "unconnected-(D4H-IO,_(DIFFIO_TX_T72p,_DIFFOUT_T72p,_DQ9T,_DQ3T)-PadD7)") (class "Default")
      (node (ref "D4") (pin "D7") (pinfunction "IO,_(DIFFIO_TX_T72p,_DIFFOUT_T72p,_DQ9T,_DQ3T)_D7") (pintype "bidirectional"))
    )
    (net (code "244") (name "unconnected-(D4H-IO,_(DIFFIO_TX_T74n,_DIFFOUT_T74n,_DQ10T,_DQ3T)-PadE6)") (class "Default")
      (node (ref "D4") (pin "E6") (pinfunction "IO,_(DIFFIO_TX_T74n,_DIFFOUT_T74n,_DQ10T,_DQ3T)_E6") (pintype "bidirectional"))
    )
    (net (code "245") (name "unconnected-(D4H-IO,_(DIFFIO_TX_T74p,_DIFFOUT_T74p,_DQ10T,_DQ3T)-PadE7)") (class "Default")
      (node (ref "D4") (pin "E7") (pinfunction "IO,_(DIFFIO_TX_T74p,_DIFFOUT_T74p,_DQ10T,_DQ3T)_E7") (pintype "bidirectional"))
    )
    (net (code "246") (name "unconnected-(D4H-IO,_(DIFFIO_TX_T76n,_DIFFOUT_T76n,_DQ10T,_DQ3T)-PadJ10)") (class "Default")
      (node (ref "D4") (pin "J10") (pinfunction "IO,_(DIFFIO_TX_T76n,_DIFFOUT_T76n,_DQ10T,_DQ3T)_J10") (pintype "bidirectional"))
    )
    (net (code "247") (name "unconnected-(D4H-IO,_(DIFFIO_TX_T76p,_DIFFOUT_T76p,_DQ10T,_DQ3T)-PadK10)") (class "Default")
      (node (ref "D4") (pin "K10") (pinfunction "IO,_(DIFFIO_TX_T76p,_DIFFOUT_T76p,_DQ10T,_DQ3T)_K10") (pintype "bidirectional"))
    )
    (net (code "248") (name "unconnected-(D4H-IO,_(DIFFIO_TX_T78n,_DIFFOUT_T78n,_DQ10T,_DQ3T)-PadF6)") (class "Default")
      (node (ref "D4") (pin "F6") (pinfunction "IO,_(DIFFIO_TX_T78n,_DIFFOUT_T78n,_DQ10T,_DQ3T)_F6") (pintype "bidirectional"))
    )
    (net (code "249") (name "unconnected-(D4H-IO,_(DIFFIO_TX_T78p,_DIFFOUT_T78p)-PadG6)") (class "Default")
      (node (ref "D4") (pin "G6") (pinfunction "IO,_(DIFFIO_TX_T78p,_DIFFOUT_T78p)_G6") (pintype "bidirectional"))
    )
    (net (code "250") (name "unconnected-(D4H-IO,_(DIFFIO_TX_T80n,_DIFFOUT_T80n)-PadG7)") (class "Default")
      (node (ref "D4") (pin "G7") (pinfunction "IO,_(DIFFIO_TX_T80n,_DIFFOUT_T80n)_G7") (pintype "bidirectional"))
    )
    (net (code "251") (name "unconnected-(D4H-IO,_(DIFFIO_TX_T80p,_DIFFOUT_T80p,_DQ10T,_DQ3T)-PadG8)") (class "Default")
      (node (ref "D4") (pin "G8") (pinfunction "IO,_(DIFFIO_TX_T80p,_DIFFOUT_T80p,_DQ10T,_DQ3T)_G8") (pintype "bidirectional"))
    )
    (net (code "252") (name "unconnected-(D4H-IO,_CLK8n,_FPLL_TL_FBn,_(DIFFIO_RX_T49n,_DIFFOUT_T49n)-PadL13)") (class "Default")
      (node (ref "D4") (pin "L13") (pinfunction "IO,_CLK8n,_FPLL_TL_FBn,_(DIFFIO_RX_T49n,_DIFFOUT_T49n)_L13") (pintype "bidirectional"))
    )
    (net (code "253") (name "unconnected-(D4H-IO,_CLK8p,_FPLL_TL_FBp,_(DIFFIO_RX_T49p,_DIFFOUT_T49p)-PadL14)") (class "Default")
      (node (ref "D4") (pin "L14") (pinfunction "IO,_CLK8p,_FPLL_TL_FBp,_(DIFFIO_RX_T49p,_DIFFOUT_T49p)_L14") (pintype "bidirectional"))
    )
    (net (code "254") (name "unconnected-(D4H-IO,_CLK9n,_(DIFFIO_RX_T41n,_DIFFOUT_T41n)-PadK15)") (class "Default")
      (node (ref "D4") (pin "K15") (pinfunction "IO,_CLK9n,_(DIFFIO_RX_T41n,_DIFFOUT_T41n)_K15") (pintype "bidirectional"))
    )
    (net (code "255") (name "unconnected-(D4H-IO,_CLK9p,_(DIFFIO_RX_T41p,_DIFFOUT_T41p)-PadL15)") (class "Default")
      (node (ref "D4") (pin "L15") (pinfunction "IO,_CLK9p,_(DIFFIO_RX_T41p,_DIFFOUT_T41p)_L15") (pintype "bidirectional"))
    )
  )
)
